# io-board-f-7.net
KiCad netlist of a schematic drawn in EAGLE
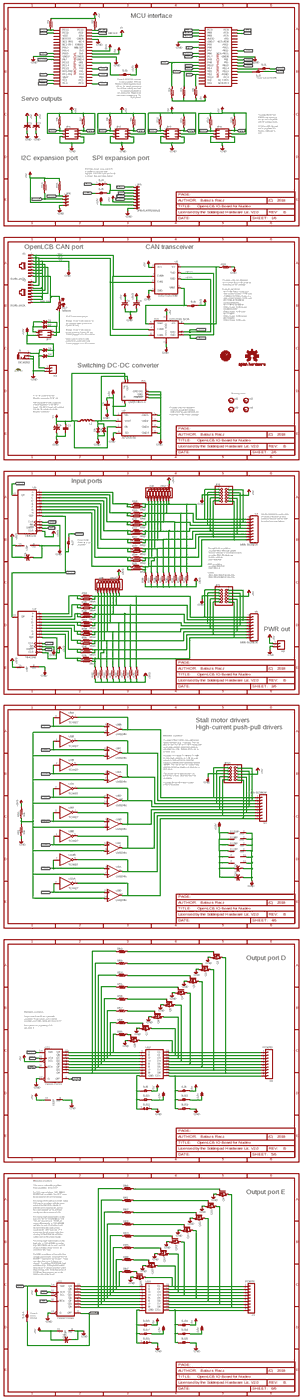
[diagram p0: schematic, sheet 1, overview]
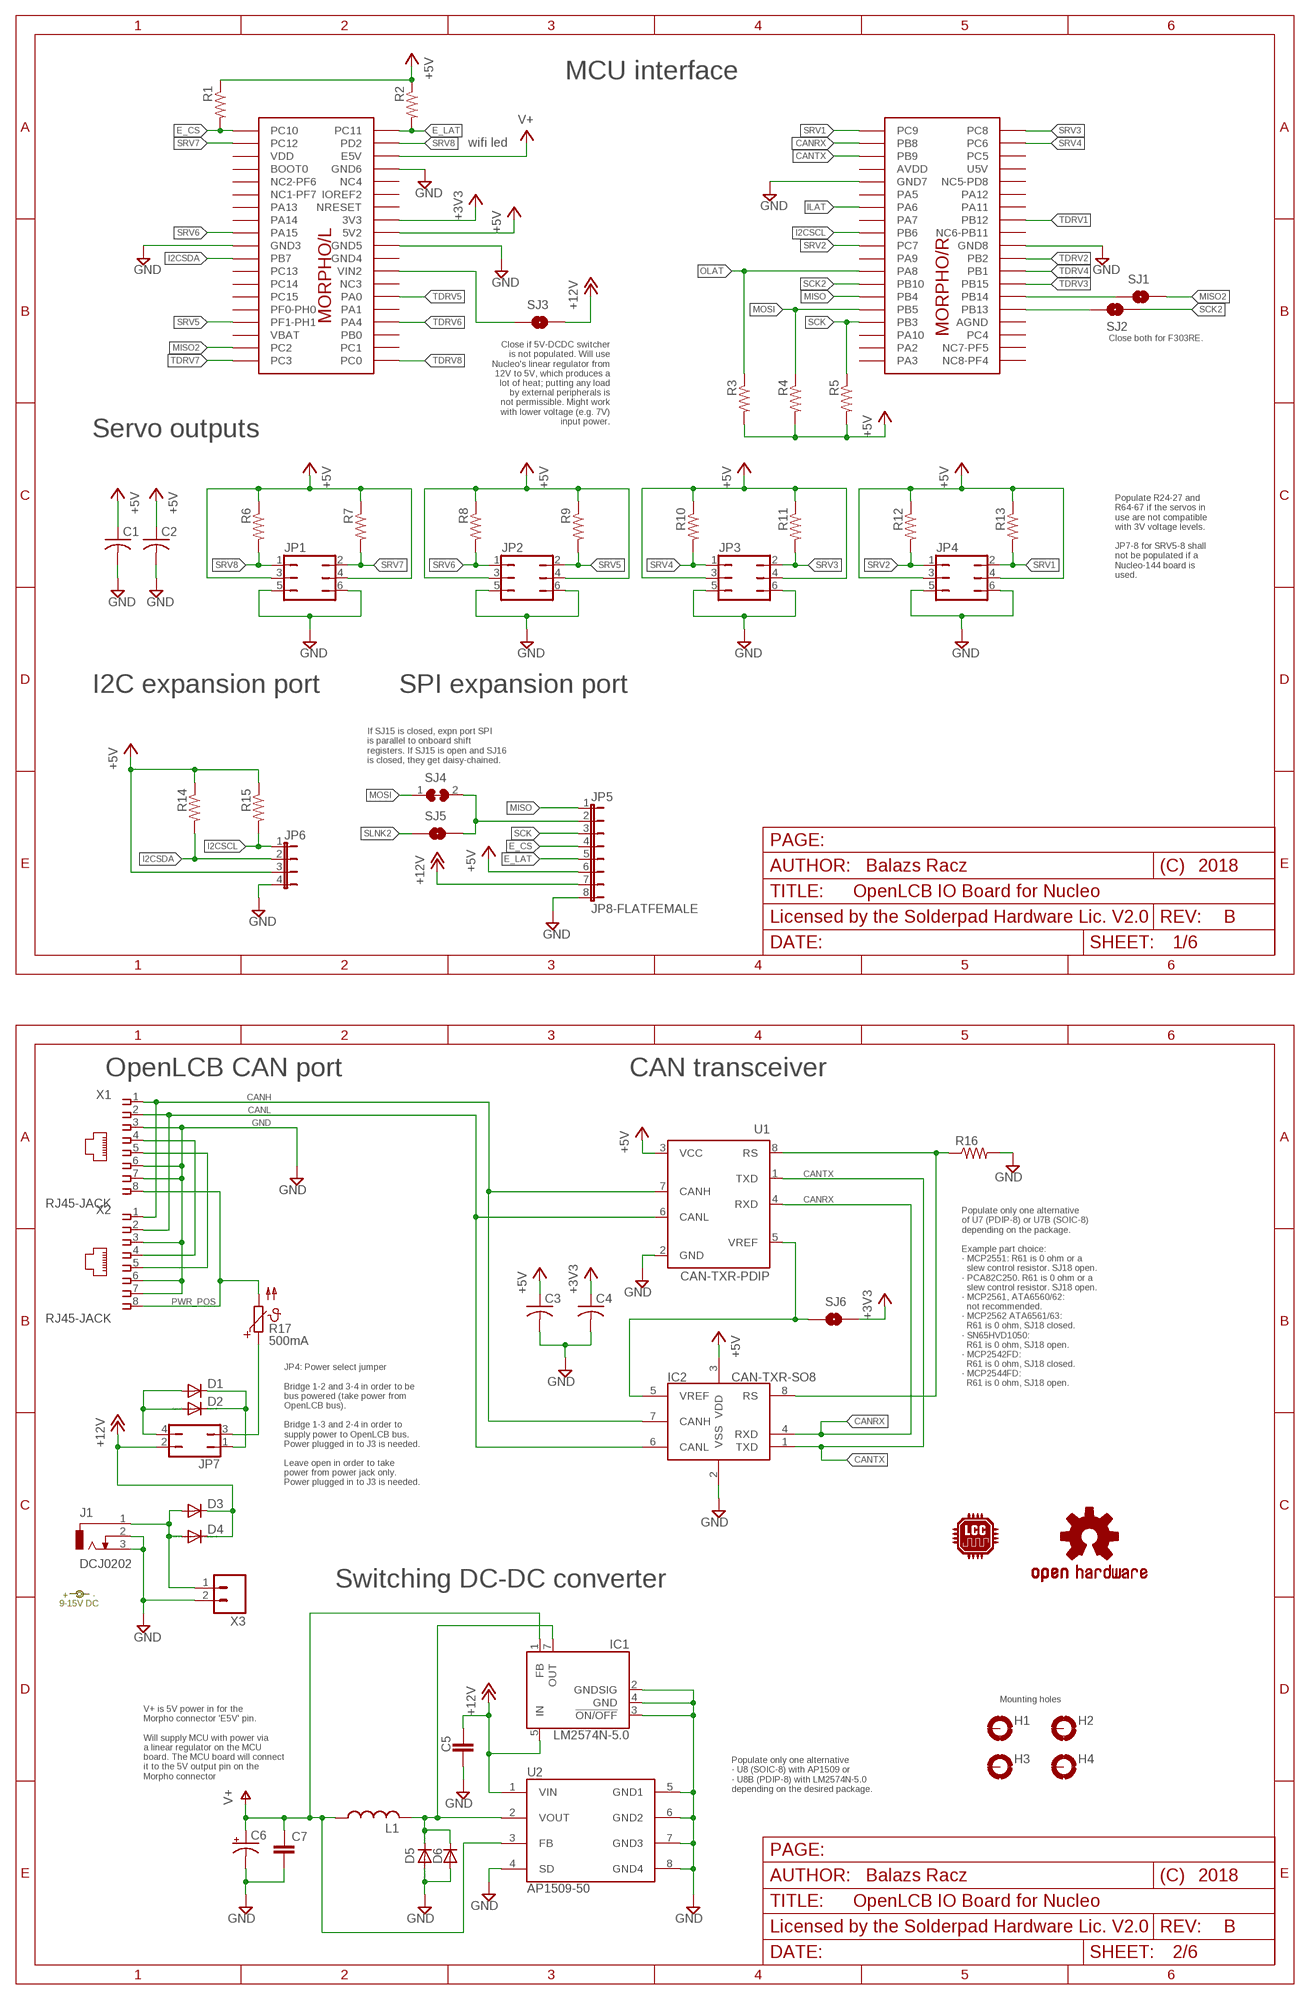
[diagram p1: schematic, sheet 1, part 1 of 4]
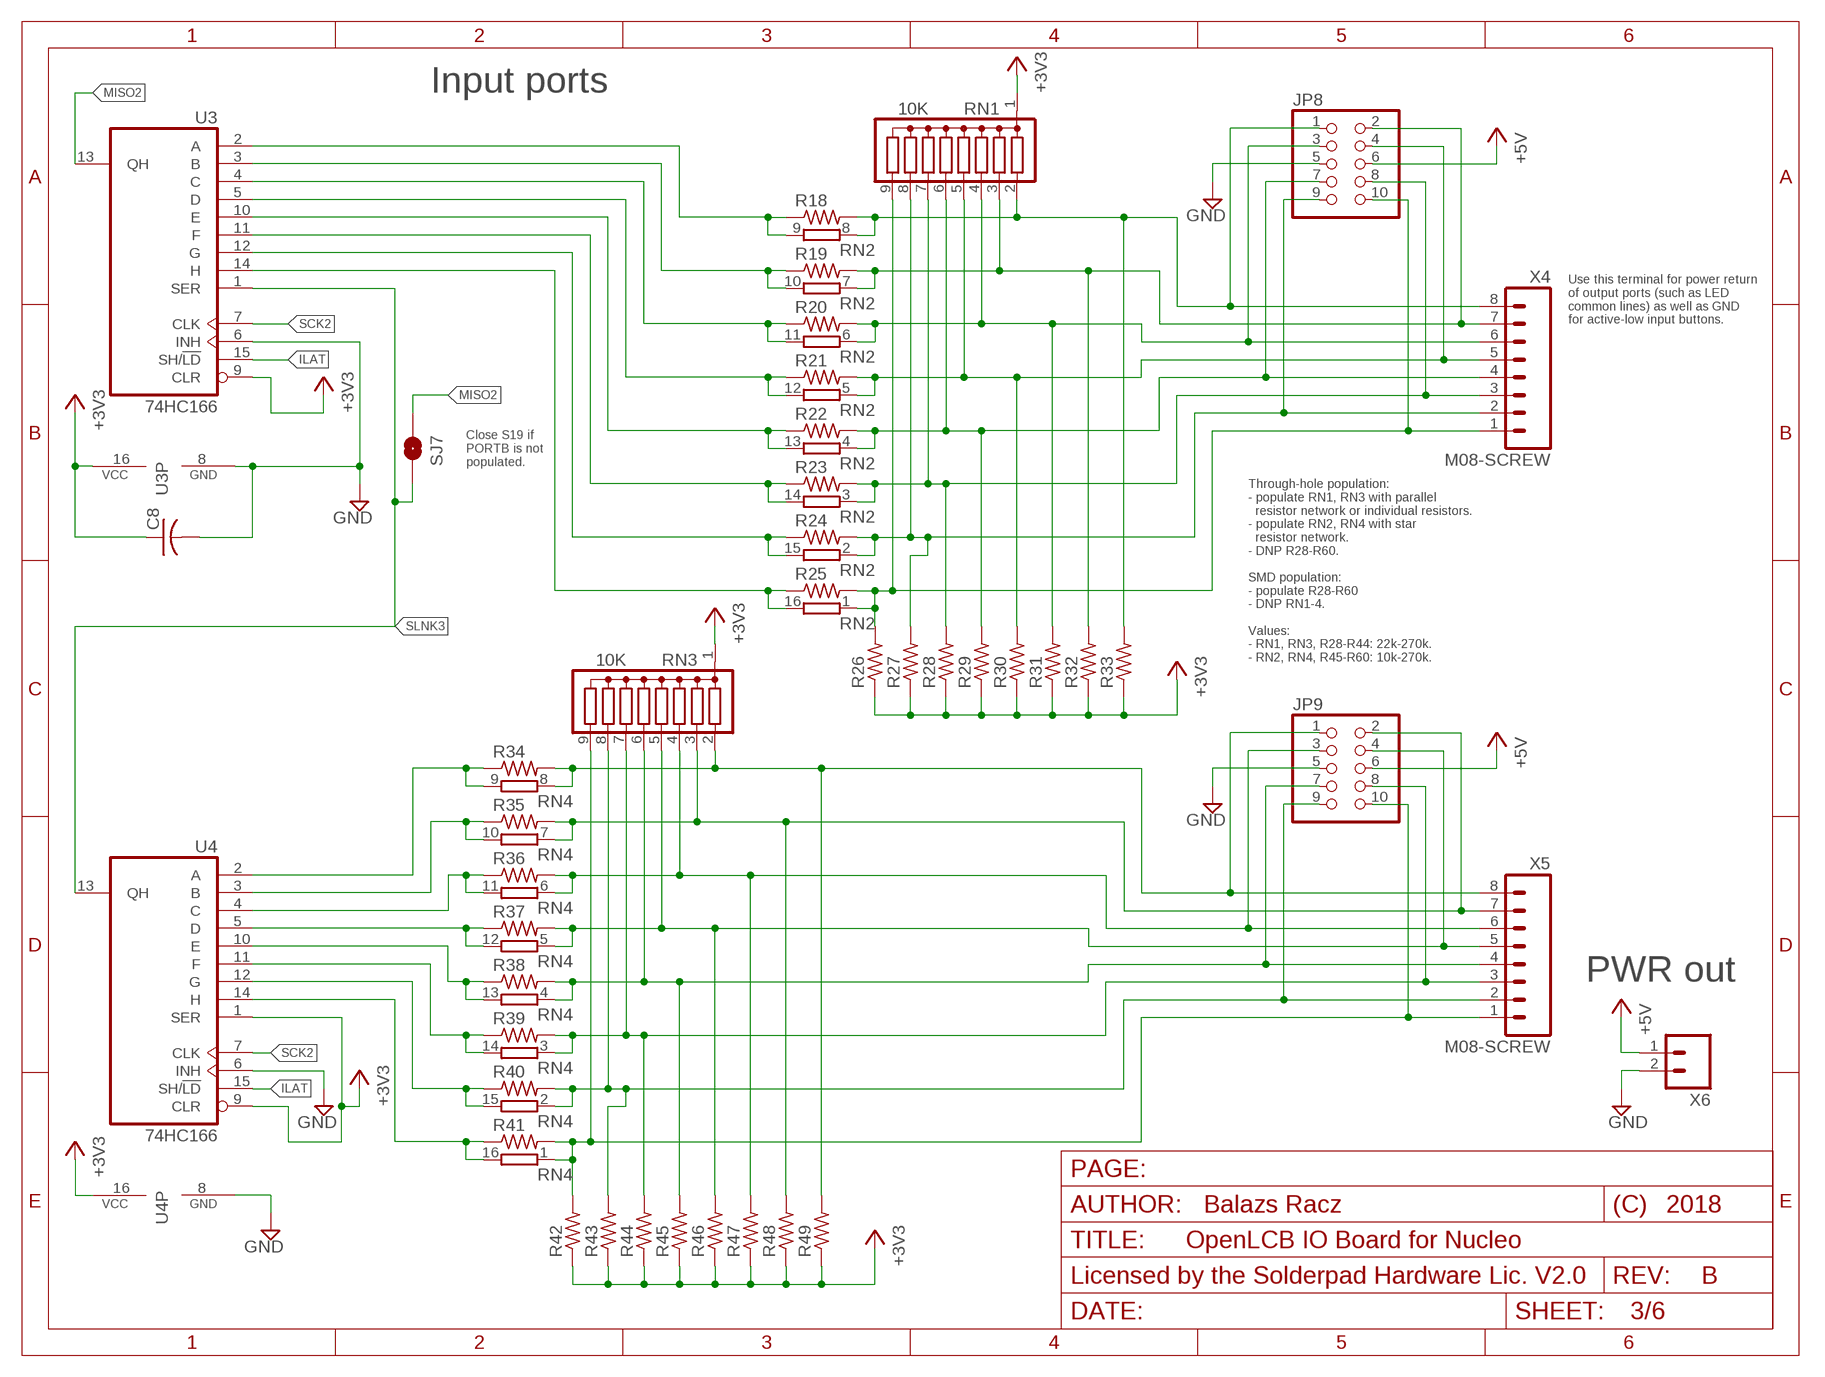
[diagram p2: schematic, sheet 1, part 2 of 4]
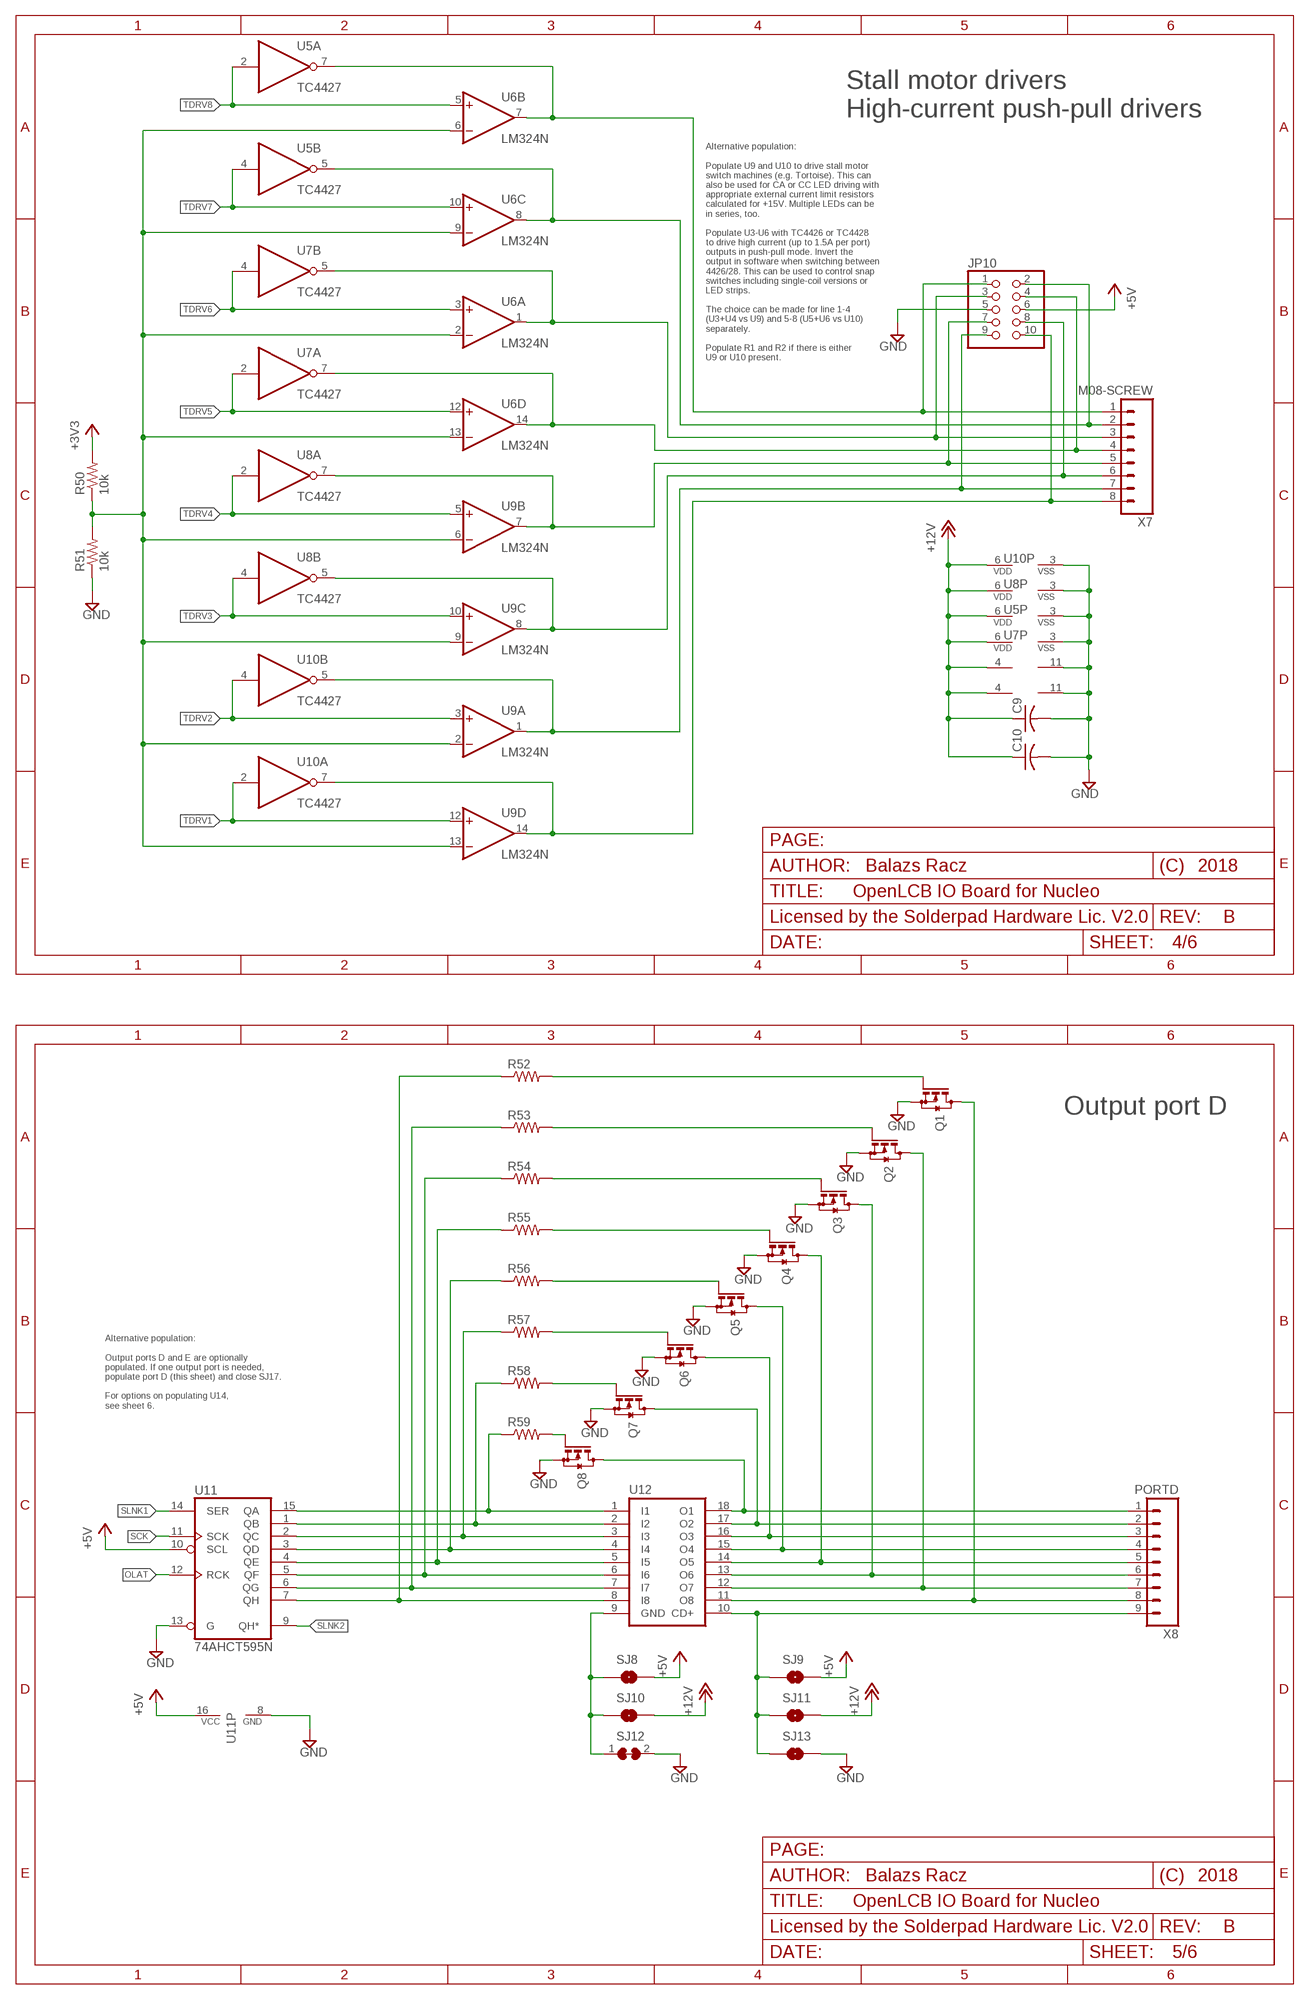
[diagram p3: schematic, sheet 1, part 3 of 4]
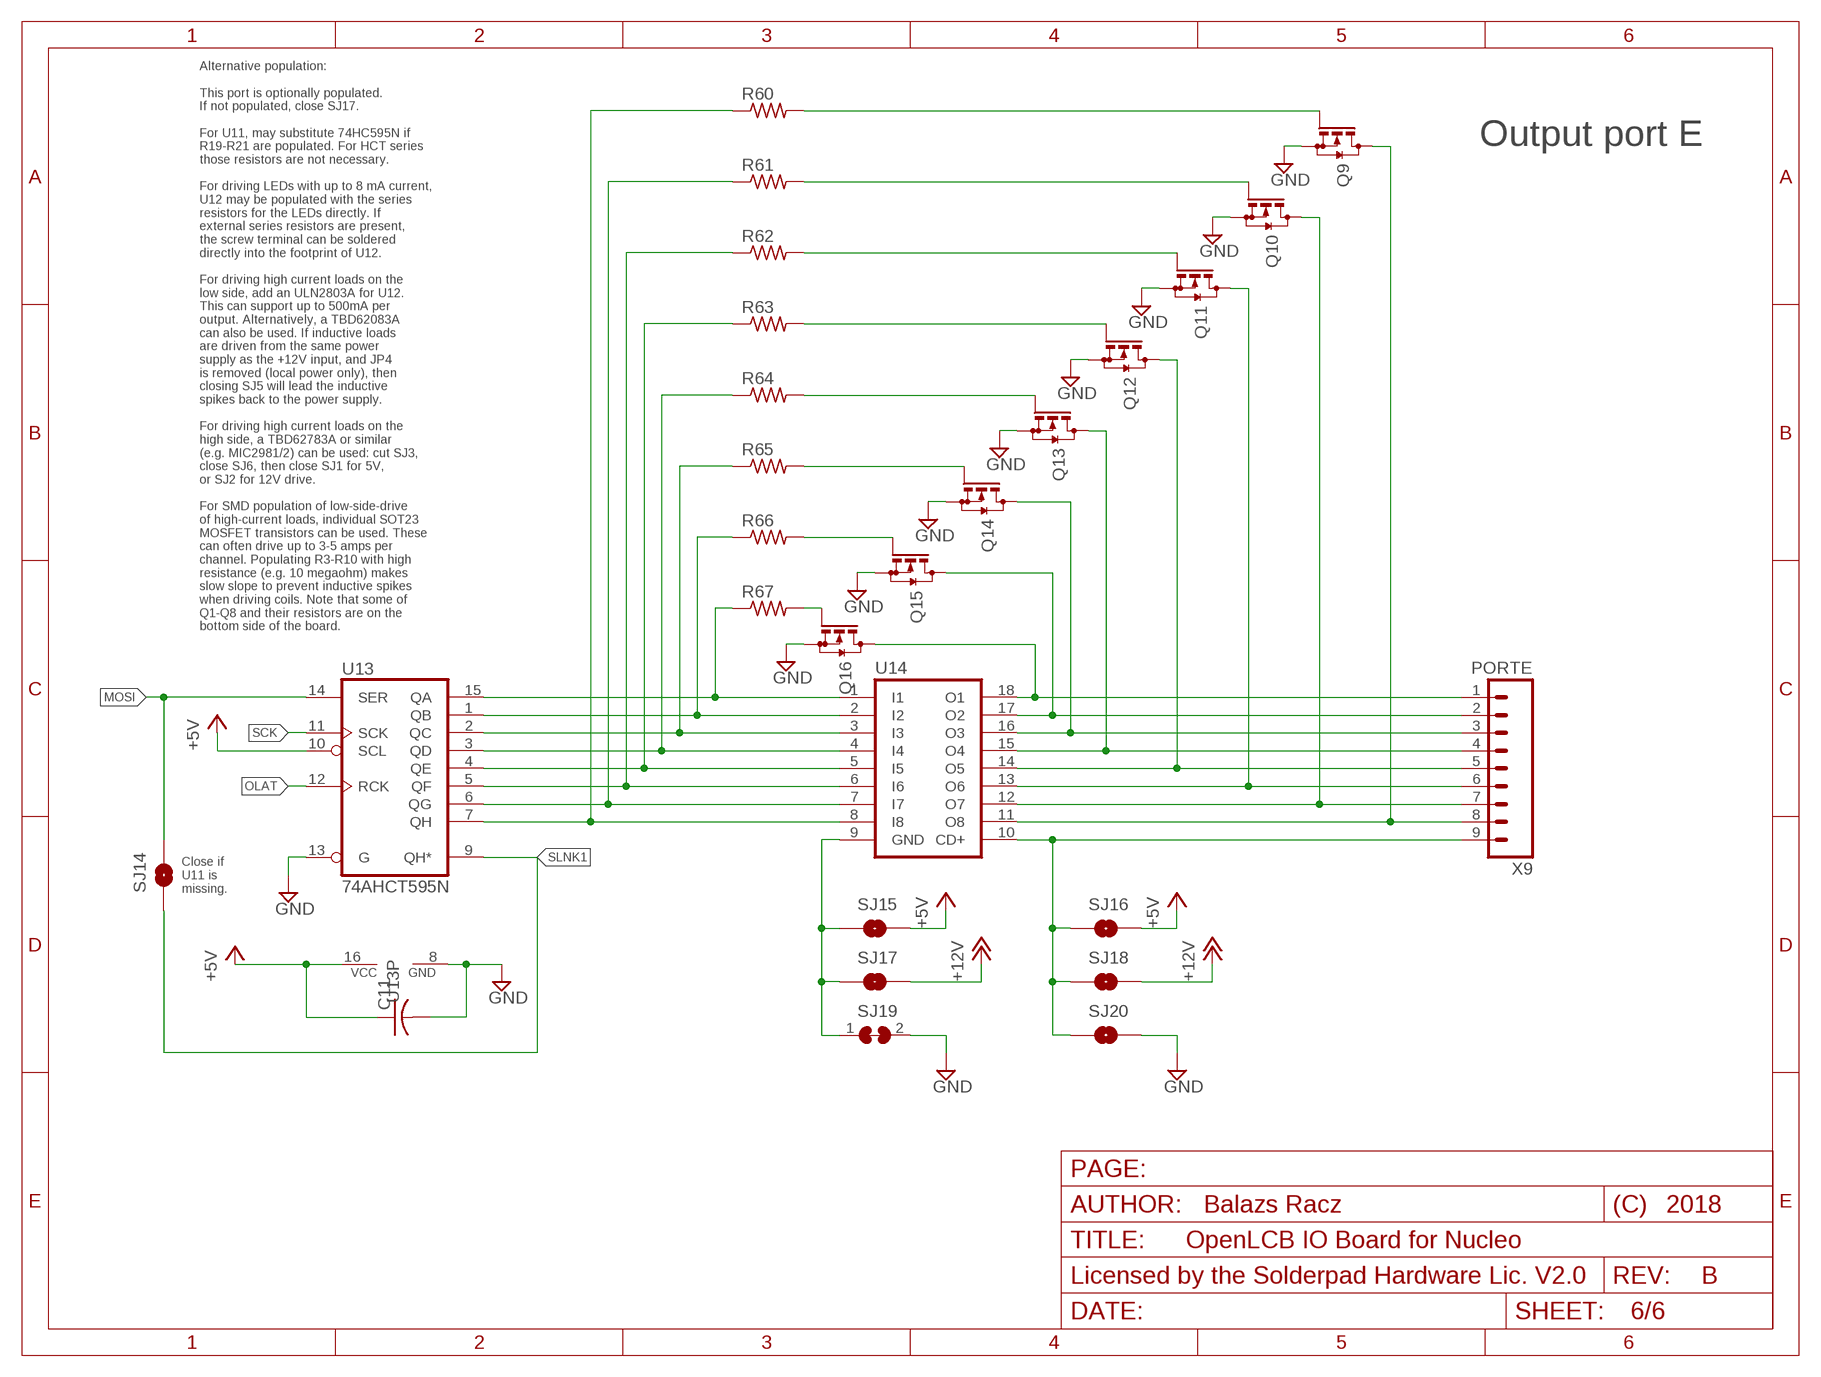
[diagram p4: schematic, sheet 1, part 4 of 4]

(export (version "E")
  (design (tool "Eeschema 10.0.6"))
  (components
    (comp (ref "C1")
      (value "C-USC1206")
      (footprint "eagle-import:C1206")
      (libsource (lib "eagle-import") (part "C-USC1206"))
    )
    (comp (ref "C2")
      (value "C-USC1206")
      (footprint "eagle-import:C1206")
      (libsource (lib "eagle-import") (part "C-USC1206"))
    )
    (comp (ref "C3")
      (value "C-USC0805")
      (footprint "eagle-import:C0805")
      (libsource (lib "eagle-import") (part "C-USC0805"))
    )
    (comp (ref "C4")
      (value "C-USC0805")
      (footprint "eagle-import:C0805")
      (libsource (lib "eagle-import") (part "C-USC0805"))
    )
    (comp (ref "C5")
      (value "C-EUC1206")
      (footprint "eagle-import:C1206")
      (libsource (lib "eagle-import") (part "C-EUC1206"))
    )
    (comp (ref "C6")
      (value "CPOL-USE2.5-5")
      (footprint "eagle-import:E2,5-5")
      (libsource (lib "eagle-import") (part "CPOL-USE2.5-5"))
    )
    (comp (ref "C7")
      (value "C-EUC1206")
      (footprint "eagle-import:C1206")
      (libsource (lib "eagle-import") (part "C-EUC1206"))
    )
    (comp (ref "C8")
      (value "C-USC0805")
      (footprint "eagle-import:C0805")
      (libsource (lib "eagle-import") (part "C-USC0805"))
    )
    (comp (ref "C9")
      (value "C-USC1206")
      (footprint "eagle-import:C1206")
      (libsource (lib "eagle-import") (part "C-USC1206"))
    )
    (comp (ref "C10")
      (value "C-USC1206")
      (footprint "eagle-import:C1206")
      (libsource (lib "eagle-import") (part "C-USC1206"))
    )
    (comp (ref "C11")
      (value "C-USC0805")
      (footprint "eagle-import:C0805")
      (libsource (lib "eagle-import") (part "C-USC0805"))
    )
    (comp (ref "D1")
      (value "DIODEDO-214AA-NODOC")
      (footprint "eagle-import:DO214AA-NODOC")
      (libsource (lib "eagle-import") (part "DIODEDO-214AA-NODOC"))
    )
    (comp (ref "D2")
      (value "DIODE-DO41-7.6")
      (footprint "eagle-import:DO41-7.6")
      (libsource (lib "eagle-import") (part "DIODE-DO41-7.6"))
    )
    (comp (ref "D3")
      (value "DIODEDO-214AA-NODOC")
      (footprint "eagle-import:DO214AA-NODOC")
      (libsource (lib "eagle-import") (part "DIODEDO-214AA-NODOC"))
    )
    (comp (ref "D4")
      (value "DIODE-DO41-7.6")
      (footprint "eagle-import:DO41-7.6")
      (libsource (lib "eagle-import") (part "DIODE-DO41-7.6"))
    )
    (comp (ref "D5")
      (value "DIODE-DO41-7.6")
      (footprint "eagle-import:DO41-7.6")
      (libsource (lib "eagle-import") (part "DIODE-DO41-7.6"))
    )
    (comp (ref "D6")
      (value "DIODEDO-214AA-NODOC")
      (footprint "eagle-import:DO214AA-NODOC")
      (libsource (lib "eagle-import") (part "DIODEDO-214AA-NODOC"))
    )
    (comp (ref "G1")
      (value "NUCLEO_64_GENERIC")
      (footprint "eagle-import:NUCLEO_BRD_BASE64")
      (libsource (lib "eagle-import") (part "NUCLEO_64_GENERIC"))
    )
    (comp (ref "H1")
      (value "MOUNT-PAD-ROUND3.3")
      (footprint "eagle-import:3,3-PAD")
      (libsource (lib "eagle-import") (part "MOUNT-PAD-ROUND3.3"))
    )
    (comp (ref "H2")
      (value "MOUNT-PAD-ROUND3.3")
      (footprint "eagle-import:3,3-PAD")
      (libsource (lib "eagle-import") (part "MOUNT-PAD-ROUND3.3"))
    )
    (comp (ref "H3")
      (value "MOUNT-PAD-ROUND3.3")
      (footprint "eagle-import:3,3-PAD")
      (libsource (lib "eagle-import") (part "MOUNT-PAD-ROUND3.3"))
    )
    (comp (ref "H4")
      (value "MOUNT-PAD-ROUND3.3")
      (footprint "eagle-import:3,3-PAD")
      (libsource (lib "eagle-import") (part "MOUNT-PAD-ROUND3.3"))
    )
    (comp (ref "IC1")
      (value "LM2574N-5.0")
      (footprint "eagle-import:DIL08")
      (libsource (lib "eagle-import") (part "LM2574?-N5.0"))
    )
    (comp (ref "IC2")
      (value "CAN-TXR-SO8")
      (footprint "eagle-import:SO-08")
      (libsource (lib "eagle-import") (part "MCP2551-SN"))
    )
    (comp (ref "J1")
      (value "DCJ0202")
      (footprint "eagle-import:DCJ0202")
      (libsource (lib "eagle-import") (part "DCJ0202"))
    )
    (comp (ref "JP1")
      (value "JP3Q")
      (footprint "eagle-import:JP3Q")
      (libsource (lib "eagle-import") (part "JP3Q"))
    )
    (comp (ref "JP2")
      (value "JP3Q")
      (footprint "eagle-import:JP3Q")
      (libsource (lib "eagle-import") (part "JP3Q"))
    )
    (comp (ref "JP3")
      (value "JP3Q")
      (footprint "eagle-import:JP3Q")
      (libsource (lib "eagle-import") (part "JP3Q"))
    )
    (comp (ref "JP4")
      (value "JP3Q")
      (footprint "eagle-import:JP3Q")
      (libsource (lib "eagle-import") (part "JP3Q"))
    )
    (comp (ref "JP5")
      (value "JP8-FLATFEMALE")
      (footprint "eagle-import:JP8F-FEM")
      (libsource (lib "eagle-import") (part "JP8-FLATFEMALE"))
    )
    (comp (ref "JP6")
      (value "JP4-FLAT")
      (footprint "eagle-import:JP4F")
      (libsource (lib "eagle-import") (part "JP4-FLAT"))
    )
    (comp (ref "JP7")
      (value "JP2Q")
      (footprint "eagle-import:JP2Q")
      (libsource (lib "eagle-import") (part "JP2Q"))
    )
    (comp (ref "JP8")
      (value "PINHD-2X5CN")
      (footprint "eagle-import:CON10M")
      (libsource (lib "eagle-import") (part "PINHD-2X5CN"))
    )
    (comp (ref "JP9")
      (value "PINHD-2X5CN")
      (footprint "eagle-import:CON10M")
      (libsource (lib "eagle-import") (part "PINHD-2X5CN"))
    )
    (comp (ref "JP10")
      (value "PINHD-2X5CN")
      (footprint "eagle-import:CON10M")
      (libsource (lib "eagle-import") (part "PINHD-2X5CN"))
    )
    (comp (ref "L1")
      (value "L-US")
      (footprint "eagle-import:L5-8,5")
      (libsource (lib "eagle-import") (part "L-US"))
    )
    (comp (ref "LG1")
      (value "LCC_LOGO")
      (footprint "eagle-import:LCC_LOGO")
      (libsource (lib "eagle-import") (part "LCC_LOGO"))
    )
    (comp (ref "LOGO1")
      (value "DOC-OSHW-LOGOM")
      (footprint "eagle-import:OSHW-LOGO-M")
      (libsource (lib "eagle-import") (part "DOC-OSHW-LOGOM"))
    )
    (comp (ref "P1")
      (value "9-15V DC")
      (footprint "eagle-import:POWER_USAGE")
      (libsource (lib "eagle-import") (part "DOC-POWER_LABEL"))
    )
    (comp (ref "Q1")
      (value "BSS123")
      (footprint "eagle-import:SOT23")
      (libsource (lib "eagle-import") (part "BSS123"))
    )
    (comp (ref "Q2")
      (value "BSS123")
      (footprint "eagle-import:SOT23")
      (libsource (lib "eagle-import") (part "BSS123"))
    )
    (comp (ref "Q3")
      (value "BSS123")
      (footprint "eagle-import:SOT23")
      (libsource (lib "eagle-import") (part "BSS123"))
    )
    (comp (ref "Q4")
      (value "BSS123")
      (footprint "eagle-import:SOT23")
      (libsource (lib "eagle-import") (part "BSS123"))
    )
    (comp (ref "Q5")
      (value "BSS123")
      (footprint "eagle-import:SOT23")
      (libsource (lib "eagle-import") (part "BSS123"))
    )
    (comp (ref "Q6")
      (value "BSS123")
      (footprint "eagle-import:SOT23")
      (libsource (lib "eagle-import") (part "BSS123"))
    )
    (comp (ref "Q7")
      (value "BSS123")
      (footprint "eagle-import:SOT23")
      (libsource (lib "eagle-import") (part "BSS123"))
    )
    (comp (ref "Q8")
      (value "BSS123")
      (footprint "eagle-import:SOT23")
      (libsource (lib "eagle-import") (part "BSS123"))
    )
    (comp (ref "Q9")
      (value "BSS123")
      (footprint "eagle-import:SOT23")
      (libsource (lib "eagle-import") (part "BSS123"))
    )
    (comp (ref "Q10")
      (value "BSS123")
      (footprint "eagle-import:SOT23")
      (libsource (lib "eagle-import") (part "BSS123"))
    )
    (comp (ref "Q11")
      (value "BSS123")
      (footprint "eagle-import:SOT23")
      (libsource (lib "eagle-import") (part "BSS123"))
    )
    (comp (ref "Q12")
      (value "BSS123")
      (footprint "eagle-import:SOT23")
      (libsource (lib "eagle-import") (part "BSS123"))
    )
    (comp (ref "Q13")
      (value "BSS123")
      (footprint "eagle-import:SOT23")
      (libsource (lib "eagle-import") (part "BSS123"))
    )
    (comp (ref "Q14")
      (value "BSS123")
      (footprint "eagle-import:SOT23")
      (libsource (lib "eagle-import") (part "BSS123"))
    )
    (comp (ref "Q15")
      (value "BSS123")
      (footprint "eagle-import:SOT23")
      (libsource (lib "eagle-import") (part "BSS123"))
    )
    (comp (ref "Q16")
      (value "BSS123")
      (footprint "eagle-import:SOT23")
      (libsource (lib "eagle-import") (part "BSS123"))
    )
    (comp (ref "R1")
      (value "R-US_R0805")
      (footprint "eagle-import:R0805")
      (libsource (lib "eagle-import") (part "rcl_334_R-US_R0805"))
    )
    (comp (ref "R2")
      (value "R-US_R0805")
      (footprint "eagle-import:R0805")
      (libsource (lib "eagle-import") (part "rcl_334_R-US_R0805"))
    )
    (comp (ref "R3")
      (value "R-US_R0805")
      (footprint "eagle-import:R0805")
      (libsource (lib "eagle-import") (part "rcl_334_R-US_R0805"))
    )
    (comp (ref "R4")
      (value "R-US_R0805")
      (footprint "eagle-import:R0805")
      (libsource (lib "eagle-import") (part "rcl_334_R-US_R0805"))
    )
    (comp (ref "R5")
      (value "R-US_R0805")
      (footprint "eagle-import:R0805")
      (libsource (lib "eagle-import") (part "rcl_334_R-US_R0805"))
    )
    (comp (ref "R6")
      (value "R-US_R0805")
      (footprint "eagle-import:R0805")
      (libsource (lib "eagle-import") (part "rcl_334_R-US_R0805"))
    )
    (comp (ref "R7")
      (value "R-US_R0805")
      (footprint "eagle-import:R0805")
      (libsource (lib "eagle-import") (part "rcl_334_R-US_R0805"))
    )
    (comp (ref "R8")
      (value "R-US_R0805")
      (footprint "eagle-import:R0805")
      (libsource (lib "eagle-import") (part "rcl_334_R-US_R0805"))
    )
    (comp (ref "R9")
      (value "R-US_R0805")
      (footprint "eagle-import:R0805")
      (libsource (lib "eagle-import") (part "rcl_334_R-US_R0805"))
    )
    (comp (ref "R10")
      (value "R-US_R0805")
      (footprint "eagle-import:R0805")
      (libsource (lib "eagle-import") (part "rcl_334_R-US_R0805"))
    )
    (comp (ref "R11")
      (value "R-US_R0805")
      (footprint "eagle-import:R0805")
      (libsource (lib "eagle-import") (part "rcl_334_R-US_R0805"))
    )
    (comp (ref "R12")
      (value "R-US_R0805")
      (footprint "eagle-import:R0805")
      (libsource (lib "eagle-import") (part "rcl_334_R-US_R0805"))
    )
    (comp (ref "R13")
      (value "R-US_R0805")
      (footprint "eagle-import:R0805")
      (libsource (lib "eagle-import") (part "rcl_334_R-US_R0805"))
    )
    (comp (ref "R14")
      (value "R-US_R0805")
      (footprint "eagle-import:R0805")
      (libsource (lib "eagle-import") (part "rcl_334_R-US_R0805"))
    )
    (comp (ref "R15")
      (value "R-US_R0805")
      (footprint "eagle-import:R0805")
      (libsource (lib "eagle-import") (part "rcl_334_R-US_R0805"))
    )
    (comp (ref "R16")
      (value "R-US_R0805")
      (footprint "eagle-import:R0805")
      (libsource (lib "eagle-import") (part "rcl_334_R-US_R0805"))
    )
    (comp (ref "R17")
      (value "500mA")
      (footprint "eagle-import:PTC1812")
      (libsource (lib "eagle-import") (part "PTC_1812"))
    )
    (comp (ref "R18")
      (value "R-US_R0603")
      (footprint "eagle-import:R0603")
      (libsource (lib "eagle-import") (part "rcl_334_R-US_R0603"))
    )
    (comp (ref "R19")
      (value "R-US_R0603")
      (footprint "eagle-import:R0603")
      (libsource (lib "eagle-import") (part "rcl_334_R-US_R0603"))
    )
    (comp (ref "R20")
      (value "R-US_R0603")
      (footprint "eagle-import:R0603")
      (libsource (lib "eagle-import") (part "rcl_334_R-US_R0603"))
    )
    (comp (ref "R21")
      (value "R-US_R0603")
      (footprint "eagle-import:R0603")
      (libsource (lib "eagle-import") (part "rcl_334_R-US_R0603"))
    )
    (comp (ref "R22")
      (value "R-US_R0603")
      (footprint "eagle-import:R0603")
      (libsource (lib "eagle-import") (part "rcl_334_R-US_R0603"))
    )
    (comp (ref "R23")
      (value "R-US_R0603")
      (footprint "eagle-import:R0603")
      (libsource (lib "eagle-import") (part "rcl_334_R-US_R0603"))
    )
    (comp (ref "R24")
      (value "R-US_R0603")
      (footprint "eagle-import:R0603")
      (libsource (lib "eagle-import") (part "rcl_334_R-US_R0603"))
    )
    (comp (ref "R25")
      (value "R-US_R0603")
      (footprint "eagle-import:R0603")
      (libsource (lib "eagle-import") (part "rcl_334_R-US_R0603"))
    )
    (comp (ref "R26")
      (value "R-US")
      (footprint "eagle-import:R0603")
      (libsource (lib "eagle-import") (part "R-US"))
    )
    (comp (ref "R27")
      (value "R-US")
      (footprint "eagle-import:R0603")
      (libsource (lib "eagle-import") (part "R-US"))
    )
    (comp (ref "R28")
      (value "R-US")
      (footprint "eagle-import:R0603")
      (libsource (lib "eagle-import") (part "R-US"))
    )
    (comp (ref "R29")
      (value "R-US")
      (footprint "eagle-import:R0603")
      (libsource (lib "eagle-import") (part "R-US"))
    )
    (comp (ref "R30")
      (value "R-US")
      (footprint "eagle-import:R0603")
      (libsource (lib "eagle-import") (part "R-US"))
    )
    (comp (ref "R31")
      (value "R-US")
      (footprint "eagle-import:R0603")
      (libsource (lib "eagle-import") (part "R-US"))
    )
    (comp (ref "R32")
      (value "R-US")
      (footprint "eagle-import:R0603")
      (libsource (lib "eagle-import") (part "R-US"))
    )
    (comp (ref "R33")
      (value "R-US")
      (footprint "eagle-import:R0603")
      (libsource (lib "eagle-import") (part "R-US"))
    )
    (comp (ref "R34")
      (value "R-US_R0603")
      (footprint "eagle-import:R0603")
      (libsource (lib "eagle-import") (part "rcl_334_R-US_R0603"))
    )
    (comp (ref "R35")
      (value "R-US_R0603")
      (footprint "eagle-import:R0603")
      (libsource (lib "eagle-import") (part "rcl_334_R-US_R0603"))
    )
    (comp (ref "R36")
      (value "R-US_R0603")
      (footprint "eagle-import:R0603")
      (libsource (lib "eagle-import") (part "rcl_334_R-US_R0603"))
    )
    (comp (ref "R37")
      (value "R-US_R0603")
      (footprint "eagle-import:R0603")
      (libsource (lib "eagle-import") (part "rcl_334_R-US_R0603"))
    )
    (comp (ref "R38")
      (value "R-US_R0603")
      (footprint "eagle-import:R0603")
      (libsource (lib "eagle-import") (part "rcl_334_R-US_R0603"))
    )
    (comp (ref "R39")
      (value "R-US_R0603")
      (footprint "eagle-import:R0603")
      (libsource (lib "eagle-import") (part "rcl_334_R-US_R0603"))
    )
    (comp (ref "R40")
      (value "R-US_R0603")
      (footprint "eagle-import:R0603")
      (libsource (lib "eagle-import") (part "rcl_334_R-US_R0603"))
    )
    (comp (ref "R41")
      (value "R-US_R0603")
      (footprint "eagle-import:R0603")
      (libsource (lib "eagle-import") (part "rcl_334_R-US_R0603"))
    )
    (comp (ref "R42")
      (value "R-US")
      (footprint "eagle-import:R0603")
      (libsource (lib "eagle-import") (part "R-US"))
    )
    (comp (ref "R43")
      (value "R-US")
      (footprint "eagle-import:R0603")
      (libsource (lib "eagle-import") (part "R-US"))
    )
    (comp (ref "R44")
      (value "R-US")
      (footprint "eagle-import:R0603")
      (libsource (lib "eagle-import") (part "R-US"))
    )
    (comp (ref "R45")
      (value "R-US")
      (footprint "eagle-import:R0603")
      (libsource (lib "eagle-import") (part "R-US"))
    )
    (comp (ref "R46")
      (value "R-US")
      (footprint "eagle-import:R0603")
      (libsource (lib "eagle-import") (part "R-US"))
    )
    (comp (ref "R47")
      (value "R-US")
      (footprint "eagle-import:R0603")
      (libsource (lib "eagle-import") (part "R-US"))
    )
    (comp (ref "R48")
      (value "R-US")
      (footprint "eagle-import:R0603")
      (libsource (lib "eagle-import") (part "R-US"))
    )
    (comp (ref "R49")
      (value "R-US")
      (footprint "eagle-import:R0603")
      (libsource (lib "eagle-import") (part "R-US"))
    )
    (comp (ref "R50")
      (value "10k")
      (footprint "eagle-import:R0805")
      (libsource (lib "eagle-import") (part "R-US_R0805"))
    )
    (comp (ref "R51")
      (value "10k")
      (footprint "eagle-import:R0805")
      (libsource (lib "eagle-import") (part "R-US_R0805"))
    )
    (comp (ref "R52")
      (value "R-US_R0603")
      (footprint "eagle-import:R0603")
      (libsource (lib "eagle-import") (part "R-US_R0603"))
    )
    (comp (ref "R53")
      (value "R-US_R0603")
      (footprint "eagle-import:R0603")
      (libsource (lib "eagle-import") (part "R-US_R0603"))
    )
    (comp (ref "R54")
      (value "R-US_R0603")
      (footprint "eagle-import:R0603")
      (libsource (lib "eagle-import") (part "R-US_R0603"))
    )
    (comp (ref "R55")
      (value "R-US_R0603")
      (footprint "eagle-import:R0603")
      (libsource (lib "eagle-import") (part "R-US_R0603"))
    )
    (comp (ref "R56")
      (value "R-US_R0603")
      (footprint "eagle-import:R0603")
      (libsource (lib "eagle-import") (part "R-US_R0603"))
    )
    (comp (ref "R57")
      (value "R-US_R0603")
      (footprint "eagle-import:R0603")
      (libsource (lib "eagle-import") (part "R-US_R0603"))
    )
    (comp (ref "R58")
      (value "R-US_R0603")
      (footprint "eagle-import:R0603")
      (libsource (lib "eagle-import") (part "R-US_R0603"))
    )
    (comp (ref "R59")
      (value "R-US_R0603")
      (footprint "eagle-import:R0603")
      (libsource (lib "eagle-import") (part "R-US_R0603"))
    )
    (comp (ref "R60")
      (value "R-US_R0603")
      (footprint "eagle-import:R0603")
      (libsource (lib "eagle-import") (part "R-US_R0603"))
    )
    (comp (ref "R61")
      (value "R-US_R0603")
      (footprint "eagle-import:R0603")
      (libsource (lib "eagle-import") (part "R-US_R0603"))
    )
    (comp (ref "R62")
      (value "R-US_R0603")
      (footprint "eagle-import:R0603")
      (libsource (lib "eagle-import") (part "R-US_R0603"))
    )
    (comp (ref "R63")
      (value "R-US_R0603")
      (footprint "eagle-import:R0603")
      (libsource (lib "eagle-import") (part "R-US_R0603"))
    )
    (comp (ref "R64")
      (value "R-US_R0603")
      (footprint "eagle-import:R0603")
      (libsource (lib "eagle-import") (part "R-US_R0603"))
    )
    (comp (ref "R65")
      (value "R-US_R0603")
      (footprint "eagle-import:R0603")
      (libsource (lib "eagle-import") (part "R-US_R0603"))
    )
    (comp (ref "R66")
      (value "R-US_R0603")
      (footprint "eagle-import:R0603")
      (libsource (lib "eagle-import") (part "R-US_R0603"))
    )
    (comp (ref "R67")
      (value "R-US_R0603")
      (footprint "eagle-import:R0603")
      (libsource (lib "eagle-import") (part "R-US_R0603"))
    )
    (comp (ref "RN1")
      (value "10K")
      (footprint "eagle-import:SIL9")
      (libsource (lib "eagle-import") (part "G08R"))
    )
    (comp (ref "RN2")
      (value "8R-P")
      (footprint "eagle-import:DIL16")
      (libsource (lib "eagle-import") (part "8R-P"))
    )
    (comp (ref "RN3")
      (value "10K")
      (footprint "eagle-import:SIL9")
      (libsource (lib "eagle-import") (part "G08R"))
    )
    (comp (ref "RN4")
      (value "8R-P")
      (footprint "eagle-import:DIL16")
      (libsource (lib "eagle-import") (part "8R-P"))
    )
    (comp (ref "SJ1")
      (value "SJRND2")
      (footprint "eagle-import:SJ_RND2")
      (libsource (lib "eagle-import") (part "SJRND2"))
    )
    (comp (ref "SJ2")
      (value "SJRND2")
      (footprint "eagle-import:SJ_RND2")
      (libsource (lib "eagle-import") (part "SJRND2"))
    )
    (comp (ref "SJ3")
      (value "SJRND2")
      (footprint "eagle-import:SJ_RND2")
      (libsource (lib "eagle-import") (part "SJRND2"))
    )
    (comp (ref "SJ4")
      (value "SJ-C")
      (footprint "eagle-import:SJW-C")
      (libsource (lib "eagle-import") (part "SJ-C"))
    )
    (comp (ref "SJ5")
      (value "SJRND2")
      (footprint "eagle-import:SJ_RND2")
      (libsource (lib "eagle-import") (part "SJRND2"))
    )
    (comp (ref "SJ6")
      (value "SJRND2")
      (footprint "eagle-import:SJ_RND2")
      (libsource (lib "eagle-import") (part "SJRND2"))
    )
    (comp (ref "SJ7")
      (value "SJRND2")
      (footprint "eagle-import:SJ_RND2")
      (libsource (lib "eagle-import") (part "SJRND2"))
    )
    (comp (ref "SJ8")
      (value "SJRND2")
      (footprint "eagle-import:SJ_RND2")
      (libsource (lib "eagle-import") (part "SJRND2"))
    )
    (comp (ref "SJ9")
      (value "SJRND2")
      (footprint "eagle-import:SJ_RND2")
      (libsource (lib "eagle-import") (part "SJRND2"))
    )
    (comp (ref "SJ10")
      (value "SJRND2")
      (footprint "eagle-import:SJ_RND2")
      (libsource (lib "eagle-import") (part "SJRND2"))
    )
    (comp (ref "SJ11")
      (value "SJRND2")
      (footprint "eagle-import:SJ_RND2")
      (libsource (lib "eagle-import") (part "SJRND2"))
    )
    (comp (ref "SJ12")
      (value "SJ-C")
      (footprint "eagle-import:SJW-C")
      (libsource (lib "eagle-import") (part "SJ-C"))
    )
    (comp (ref "SJ13")
      (value "SJRND2")
      (footprint "eagle-import:SJ_RND2")
      (libsource (lib "eagle-import") (part "SJRND2"))
    )
    (comp (ref "SJ14")
      (value "SJRND2")
      (footprint "eagle-import:SJ_RND2")
      (libsource (lib "eagle-import") (part "SJRND2"))
    )
    (comp (ref "SJ15")
      (value "SJRND2")
      (footprint "eagle-import:SJ_RND2")
      (libsource (lib "eagle-import") (part "SJRND2"))
    )
    (comp (ref "SJ16")
      (value "SJRND2")
      (footprint "eagle-import:SJ_RND2")
      (libsource (lib "eagle-import") (part "SJRND2"))
    )
    (comp (ref "SJ17")
      (value "SJRND2")
      (footprint "eagle-import:SJ_RND2")
      (libsource (lib "eagle-import") (part "SJRND2"))
    )
    (comp (ref "SJ18")
      (value "SJRND2")
      (footprint "eagle-import:SJ_RND2")
      (libsource (lib "eagle-import") (part "SJRND2"))
    )
    (comp (ref "SJ19")
      (value "SJ-C")
      (footprint "eagle-import:SJW-C")
      (libsource (lib "eagle-import") (part "SJ-C"))
    )
    (comp (ref "SJ20")
      (value "SJRND2")
      (footprint "eagle-import:SJ_RND2")
      (libsource (lib "eagle-import") (part "SJRND2"))
    )
    (comp (ref "U1")
      (value "CAN-TXR-PDIP")
      (footprint "eagle-import:DIL08")
      (libsource (lib "eagle-import") (part "PCA82C250"))
    )
    (comp (ref "U2")
      (value "AP1509-50")
      (footprint "eagle-import:SO-08")
      (libsource (lib "eagle-import") (part "AP1509"))
    )
    (comp (ref "U3")
      (value "74HC166")
      (footprint "eagle-import:DIL16")
      (libsource (lib "eagle-import") (part "74166N"))
    )
    (comp (ref "U4")
      (value "74HC166")
      (footprint "eagle-import:DIL16")
      (libsource (lib "eagle-import") (part "74166N"))
    )
    (comp (ref "U5")
      (value "TC4427")
      (footprint "eagle-import:DIL08-LONG")
      (libsource (lib "eagle-import") (part "TC4426APDIP"))
    )
    (comp (ref "U6")
      (value "LM324N")
      (footprint "eagle-import:DIL14")
      (libsource (lib "eagle-import") (part "LM324N"))
    )
    (comp (ref "U7")
      (value "TC4427")
      (footprint "eagle-import:DIL08-LONG")
      (libsource (lib "eagle-import") (part "TC4426APDIP"))
    )
    (comp (ref "U8")
      (value "TC4427")
      (footprint "eagle-import:DIL08-LONG")
      (libsource (lib "eagle-import") (part "TC4426APDIP"))
    )
    (comp (ref "U9")
      (value "LM324N")
      (footprint "eagle-import:DIL14")
      (libsource (lib "eagle-import") (part "LM324N"))
    )
    (comp (ref "U10")
      (value "TC4427")
      (footprint "eagle-import:DIL08-LONG")
      (libsource (lib "eagle-import") (part "TC4426APDIP"))
    )
    (comp (ref "U11")
      (value "74AHCT595N")
      (footprint "eagle-import:DIL16")
      (libsource (lib "eagle-import") (part "74595NHCT"))
    )
    (comp (ref "U12")
      (value "ULN2803A")
      (footprint "eagle-import:DIL18-THIN")
      (libsource (lib "eagle-import") (part "ULN2803A"))
    )
    (comp (ref "U13")
      (value "74AHCT595N")
      (footprint "eagle-import:DIL16")
      (libsource (lib "eagle-import") (part "74595NHCT"))
    )
    (comp (ref "U14")
      (value "ULN2803A")
      (footprint "eagle-import:DIL18-THIN")
      (libsource (lib "eagle-import") (part "ULN2803A"))
    )
    (comp (ref "X1")
      (value "RJ45-JACK")
      (footprint "eagle-import:RJ45-PULSE-E5J88")
      (libsource (lib "eagle-import") (part "RJ45-JACKRJ45-PULSE-E5J00"))
    )
    (comp (ref "X2")
      (value "RJ45-JACK")
      (footprint "eagle-import:RJ45-PULSE-E5J88")
      (libsource (lib "eagle-import") (part "RJ45-JACKRJ45-PULSE-E5J00"))
    )
    (comp (ref "X3")
      (value "CONNECTOR-M023.5MM-LOCK")
      (footprint "eagle-import:SCREWTERMINAL-3.5MM-2_LOCK")
      (libsource (lib "eagle-import") (part "CONNECTOR-M023.5MM-LOCK"))
    )
    (comp (ref "X4")
      (value "M08-SCREW")
      (footprint "eagle-import:1X08_TERMINAL")
      (libsource (lib "eagle-import") (part "M08-SCREW"))
    )
    (comp (ref "X5")
      (value "M08-SCREW")
      (footprint "eagle-import:1X08_TERMINAL")
      (libsource (lib "eagle-import") (part "M08-SCREW"))
    )
    (comp (ref "X6")
      (value "CONNECTOR-M023.5MM-LOCK")
      (footprint "eagle-import:SCREWTERMINAL-3.5MM-2_LOCK")
      (libsource (lib "eagle-import") (part "CONNECTOR-M023.5MM-LOCK"))
    )
    (comp (ref "X7")
      (value "M08-SCREW")
      (footprint "eagle-import:1X08_TERMINAL")
      (libsource (lib "eagle-import") (part "M08-SCREW"))
    )
    (comp (ref "X8")
      (value "PORTD")
      (footprint "eagle-import:1X09_TERMINAL")
      (libsource (lib "eagle-import") (part "M09-SCREW"))
    )
    (comp (ref "X9")
      (value "PORTE")
      (footprint "eagle-import:1X09_TERMINAL")
      (libsource (lib "eagle-import") (part "M09-SCREW"))
    )
  )
  (nets
    (net (code "1") (name "+3V3") (class "Default")
      (node (ref "C4") (pin "1") (pinfunction "1_1") (pintype "passive"))
      (node (ref "C8") (pin "1") (pinfunction "1_1") (pintype "passive"))
      (node (ref "G1") (pin "3V3") (pinfunction "3V3_3V3") (pintype "power_in"))
      (node (ref "R26") (pin "1") (pinfunction "1_1") (pintype "passive"))
      (node (ref "R27") (pin "1") (pinfunction "1_1") (pintype "passive"))
      (node (ref "R28") (pin "1") (pinfunction "1_1") (pintype "passive"))
      (node (ref "R29") (pin "1") (pinfunction "1_1") (pintype "passive"))
      (node (ref "R30") (pin "1") (pinfunction "1_1") (pintype "passive"))
      (node (ref "R31") (pin "1") (pinfunction "1_1") (pintype "passive"))
      (node (ref "R32") (pin "1") (pinfunction "1_1") (pintype "passive"))
      (node (ref "R33") (pin "1") (pinfunction "1_1") (pintype "passive"))
      (node (ref "R42") (pin "1") (pinfunction "1_1") (pintype "passive"))
      (node (ref "R43") (pin "1") (pinfunction "1_1") (pintype "passive"))
      (node (ref "R44") (pin "1") (pinfunction "1_1") (pintype "passive"))
      (node (ref "R45") (pin "1") (pinfunction "1_1") (pintype "passive"))
      (node (ref "R46") (pin "1") (pinfunction "1_1") (pintype "passive"))
      (node (ref "R47") (pin "1") (pinfunction "1_1") (pintype "passive"))
      (node (ref "R48") (pin "1") (pinfunction "1_1") (pintype "passive"))
      (node (ref "R49") (pin "1") (pinfunction "1_1") (pintype "passive"))
      (node (ref "R50") (pin "2") (pinfunction "2_2") (pintype "passive"))
      (node (ref "RN1") (pin "1") (pinfunction "1_1") (pintype "passive"))
      (node (ref "RN3") (pin "1") (pinfunction "1_1") (pintype "passive"))
      (node (ref "SJ6") (pin "P$1") (pinfunction "1_P$1") (pintype "passive"))
      (node (ref "U3") (pin "16") (pinfunction "VCC_16") (pintype "power_in"))
      (node (ref "U3") (pin "9") (pinfunction "CLR_9") (pintype "input"))
      (node (ref "U4") (pin "1") (pinfunction "SER_1") (pintype "input"))
      (node (ref "U4") (pin "16") (pinfunction "VCC_16") (pintype "power_in"))
      (node (ref "U4") (pin "9") (pinfunction "CLR_9") (pintype "input"))
    )
    (net (code "2") (name "+5V") (class "Default")
      (node (ref "C1") (pin "1") (pinfunction "1_1") (pintype "passive"))
      (node (ref "C11") (pin "1") (pinfunction "1_1") (pintype "passive"))
      (node (ref "C2") (pin "1") (pinfunction "1_1") (pintype "passive"))
      (node (ref "C3") (pin "1") (pinfunction "1_1") (pintype "passive"))
      (node (ref "G1") (pin "5V2") (pinfunction "5V2_5V2") (pintype "power_in"))
      (node (ref "IC2") (pin "3") (pinfunction "VDD_3") (pintype "power_in"))
      (node (ref "JP1") (pin "3") (pinfunction "3_3") (pintype "passive"))
      (node (ref "JP1") (pin "4") (pinfunction "4_4") (pintype "passive"))
      (node (ref "JP10") (pin "6") (pinfunction "6_6") (pintype "passive"))
      (node (ref "JP2") (pin "3") (pinfunction "3_3") (pintype "passive"))
      (node (ref "JP2") (pin "4") (pinfunction "4_4") (pintype "passive"))
      (node (ref "JP3") (pin "3") (pinfunction "3_3") (pintype "passive"))
      (node (ref "JP3") (pin "4") (pinfunction "4_4") (pintype "passive"))
      (node (ref "JP4") (pin "3") (pinfunction "3_3") (pintype "passive"))
      (node (ref "JP4") (pin "4") (pinfunction "4_4") (pintype "passive"))
      (node (ref "JP5") (pin "6") (pinfunction "6_6") (pintype "passive"))
      (node (ref "JP6") (pin "3") (pinfunction "3_3") (pintype "passive"))
      (node (ref "JP8") (pin "6") (pinfunction "6_6") (pintype "passive"))
      (node (ref "JP9") (pin "6") (pinfunction "6_6") (pintype "passive"))
      (node (ref "R1") (pin "1") (pinfunction "1_1") (pintype "passive"))
      (node (ref "R10") (pin "1") (pinfunction "1_1") (pintype "passive"))
      (node (ref "R11") (pin "1") (pinfunction "1_1") (pintype "passive"))
      (node (ref "R12") (pin "1") (pinfunction "1_1") (pintype "passive"))
      (node (ref "R13") (pin "1") (pinfunction "1_1") (pintype "passive"))
      (node (ref "R14") (pin "1") (pinfunction "1_1") (pintype "passive"))
      (node (ref "R15") (pin "1") (pinfunction "1_1") (pintype "passive"))
      (node (ref "R2") (pin "1") (pinfunction "1_1") (pintype "passive"))
      (node (ref "R3") (pin "2") (pinfunction "2_2") (pintype "passive"))
      (node (ref "R4") (pin "2") (pinfunction "2_2") (pintype "passive"))
      (node (ref "R5") (pin "2") (pinfunction "2_2") (pintype "passive"))
      (node (ref "R6") (pin "1") (pinfunction "1_1") (pintype "passive"))
      (node (ref "R7") (pin "1") (pinfunction "1_1") (pintype "passive"))
      (node (ref "R8") (pin "1") (pinfunction "1_1") (pintype "passive"))
      (node (ref "R9") (pin "1") (pinfunction "1_1") (pintype "passive"))
      (node (ref "SJ15") (pin "P$2") (pinfunction "2_P$2") (pintype "passive"))
      (node (ref "SJ16") (pin "P$2") (pinfunction "2_P$2") (pintype "passive"))
      (node (ref "SJ8") (pin "P$2") (pinfunction "2_P$2") (pintype "passive"))
      (node (ref "SJ9") (pin "P$2") (pinfunction "2_P$2") (pintype "passive"))
      (node (ref "U1") (pin "3") (pinfunction "VCC_3") (pintype "power_in"))
      (node (ref "U11") (pin "10") (pinfunction "SCL_10") (pintype "input"))
      (node (ref "U11") (pin "16") (pinfunction "VCC_16") (pintype "power_in"))
      (node (ref "U13") (pin "10") (pinfunction "SCL_10") (pintype "input"))
      (node (ref "U13") (pin "16") (pinfunction "VCC_16") (pintype "power_in"))
      (node (ref "X6") (pin "1") (pinfunction "1_1") (pintype "passive"))
    )
    (net (code "3") (name "+12V") (class "Default")
      (node (ref "C10") (pin "1") (pinfunction "1_1") (pintype "passive"))
      (node (ref "C5") (pin "1") (pinfunction "1_1") (pintype "passive"))
      (node (ref "C9") (pin "1") (pinfunction "1_1") (pintype "passive"))
      (node (ref "D3") (pin "C") (pinfunction "C_C") (pintype "passive"))
      (node (ref "D4") (pin "C") (pinfunction "C_C") (pintype "passive"))
      (node (ref "IC1") (pin "5") (pinfunction "IN_5") (pintype "input"))
      (node (ref "JP5") (pin "7") (pinfunction "7_7") (pintype "passive"))
      (node (ref "JP7") (pin "2") (pinfunction "2_2") (pintype "passive"))
      (node (ref "SJ10") (pin "P$2") (pinfunction "2_P$2") (pintype "passive"))
      (node (ref "SJ11") (pin "P$2") (pinfunction "2_P$2") (pintype "passive"))
      (node (ref "SJ17") (pin "P$2") (pinfunction "2_P$2") (pintype "passive"))
      (node (ref "SJ18") (pin "P$2") (pinfunction "2_P$2") (pintype "passive"))
      (node (ref "SJ3") (pin "P$2") (pinfunction "2_P$2") (pintype "passive"))
      (node (ref "U10") (pin "6") (pinfunction "VDD_6") (pintype "power_in"))
      (node (ref "U2") (pin "1") (pinfunction "VIN_1") (pintype "bidirectional"))
      (node (ref "U5") (pin "6") (pinfunction "VDD_6") (pintype "power_in"))
      (node (ref "U6") (pin "4") (pinfunction "V+_4") (pintype "power_in"))
      (node (ref "U7") (pin "6") (pinfunction "VDD_6") (pintype "power_in"))
      (node (ref "U8") (pin "6") (pinfunction "VDD_6") (pintype "power_in"))
      (node (ref "U9") (pin "4") (pinfunction "V+_4") (pintype "power_in"))
    )
    (net (code "4") (name "/AGND") (class "Default")
      (node (ref "G1") (pin "AGND") (pinfunction "AGND_AGND") (pintype "power_in"))
    )
    (net (code "5") (name "/AVDD") (class "Default")
      (node (ref "G1") (pin "AVDD") (pinfunction "AVDD_AVDD") (pintype "power_in"))
    )
    (net (code "6") (name "/CANH") (class "Default")
      (node (ref "IC2") (pin "7") (pinfunction "CANH_7") (pintype "bidirectional"))
      (node (ref "U1") (pin "7") (pinfunction "CANH_7") (pintype "bidirectional"))
      (node (ref "X1") (pin "1") (pinfunction "1_1") (pintype "passive"))
      (node (ref "X2") (pin "1") (pinfunction "1_1") (pintype "passive"))
    )
    (net (code "7") (name "/CANL") (class "Default")
      (node (ref "IC2") (pin "6") (pinfunction "CANL_6") (pintype "bidirectional"))
      (node (ref "U1") (pin "6") (pinfunction "CANL_6") (pintype "bidirectional"))
      (node (ref "X1") (pin "2") (pinfunction "2_2") (pintype "passive"))
      (node (ref "X2") (pin "2") (pinfunction "2_2") (pintype "passive"))
    )
    (net (code "8") (name "/GND4") (class "Default")
      (node (ref "G1") (pin "GND4") (pinfunction "GND4_GND4") (pintype "power_in"))
    )
    (net (code "9") (name "/PWR_POS") (class "Default")
      (node (ref "R17") (pin "2") (pinfunction "2_2") (pintype "passive"))
      (node (ref "X1") (pin "8") (pinfunction "8_8") (pintype "passive"))
      (node (ref "X2") (pin "8") (pinfunction "8_8") (pintype "passive"))
    )
    (net (code "10") (name "/U5V") (class "Default")
      (node (ref "G1") (pin "U5V") (pinfunction "U5V_U5V") (pintype "power_in"))
    )
    (net (code "11") (name "/VBAT") (class "Default")
      (node (ref "G1") (pin "VBAT") (pinfunction "VBAT_VBAT") (pintype "power_in"))
    )
    (net (code "12") (name "/VDD") (class "Default")
      (node (ref "G1") (pin "VDD") (pinfunction "VDD_VDD") (pintype "power_in"))
    )
    (net (code "13") (name "CANRX") (class "Default")
      (node (ref "G1") (pin "PB8") (pinfunction "PB8_PB8") (pintype "bidirectional"))
      (node (ref "IC2") (pin "4") (pinfunction "RXD_4") (pintype "bidirectional"))
      (node (ref "U1") (pin "4") (pinfunction "RXD_4") (pintype "output"))
    )
    (net (code "14") (name "CANTX") (class "Default")
      (node (ref "G1") (pin "PB9") (pinfunction "PB9_PB9") (pintype "bidirectional"))
      (node (ref "IC2") (pin "1") (pinfunction "TXD_1") (pintype "bidirectional"))
      (node (ref "U1") (pin "1") (pinfunction "TXD_1") (pintype "input"))
    )
    (net (code "15") (name "E_CS") (class "Default")
      (node (ref "G1") (pin "PC10") (pinfunction "PC10_PC10") (pintype "bidirectional"))
      (node (ref "JP5") (pin "4") (pinfunction "4_4") (pintype "passive"))
      (node (ref "R1") (pin "2") (pinfunction "2_2") (pintype "passive"))
    )
    (net (code "16") (name "E_LAT") (class "Default")
      (node (ref "G1") (pin "PC11") (pinfunction "PC11_PC11") (pintype "bidirectional"))
      (node (ref "JP5") (pin "5") (pinfunction "5_5") (pintype "passive"))
      (node (ref "R2") (pin "2") (pinfunction "2_2") (pintype "passive"))
    )
    (net (code "17") (name "GND") (class "Default")
      (node (ref "C1") (pin "2") (pinfunction "2_2") (pintype "passive"))
      (node (ref "C10") (pin "2") (pinfunction "2_2") (pintype "passive"))
      (node (ref "C11") (pin "2") (pinfunction "2_2") (pintype "passive"))
      (node (ref "C2") (pin "2") (pinfunction "2_2") (pintype "passive"))
      (node (ref "C3") (pin "2") (pinfunction "2_2") (pintype "passive"))
      (node (ref "C4") (pin "2") (pinfunction "2_2") (pintype "passive"))
      (node (ref "C5") (pin "2") (pinfunction "2_2") (pintype "passive"))
      (node (ref "C6") (pin "-") (pinfunction "-_-") (pintype "passive"))
      (node (ref "C7") (pin "2") (pinfunction "2_2") (pintype "passive"))
      (node (ref "C8") (pin "2") (pinfunction "2_2") (pintype "passive"))
      (node (ref "C9") (pin "2") (pinfunction "2_2") (pintype "passive"))
      (node (ref "D5") (pin "A") (pinfunction "A_A") (pintype "passive"))
      (node (ref "D6") (pin "A") (pinfunction "A_A") (pintype "passive"))
      (node (ref "G1") (pin "GND3") (pinfunction "GND3_GND3") (pintype "power_in"))
      (node (ref "G1") (pin "GND5") (pinfunction "GND5_GND5") (pintype "power_in"))
      (node (ref "G1") (pin "GND6") (pinfunction "GND6_GND6") (pintype "power_in"))
      (node (ref "G1") (pin "GND7") (pinfunction "GND7_GND7") (pintype "power_in"))
      (node (ref "G1") (pin "GND8") (pinfunction "GND8_GND8") (pintype "power_in"))
      (node (ref "IC1") (pin "2") (pinfunction "GNDSIG_2") (pintype "input"))
      (node (ref "IC1") (pin "3") (pinfunction "~{ON/OFF}_3") (pintype "input"))
      (node (ref "IC1") (pin "4") (pinfunction "GND_4") (pintype "power_in"))
      (node (ref "IC2") (pin "2") (pinfunction "VSS_2") (pintype "power_in"))
      (node (ref "J1") (pin "2") (pinfunction "2_2") (pintype "passive"))
      (node (ref "J1") (pin "3") (pinfunction "3_3") (pintype "passive"))
      (node (ref "JP1") (pin "5") (pinfunction "5_5") (pintype "passive"))
      (node (ref "JP1") (pin "6") (pinfunction "6_6") (pintype "passive"))
      (node (ref "JP10") (pin "5") (pinfunction "5_5") (pintype "passive"))
      (node (ref "JP2") (pin "5") (pinfunction "5_5") (pintype "passive"))
      (node (ref "JP2") (pin "6") (pinfunction "6_6") (pintype "passive"))
      (node (ref "JP3") (pin "5") (pinfunction "5_5") (pintype "passive"))
      (node (ref "JP3") (pin "6") (pinfunction "6_6") (pintype "passive"))
      (node (ref "JP4") (pin "5") (pinfunction "5_5") (pintype "passive"))
      (node (ref "JP4") (pin "6") (pinfunction "6_6") (pintype "passive"))
      (node (ref "JP5") (pin "8") (pinfunction "8_8") (pintype "passive"))
      (node (ref "JP6") (pin "4") (pinfunction "4_4") (pintype "passive"))
      (node (ref "JP8") (pin "5") (pinfunction "5_5") (pintype "passive"))
      (node (ref "JP9") (pin "5") (pinfunction "5_5") (pintype "passive"))
      (node (ref "Q1") (pin "2") (pinfunction "S_2") (pintype "passive"))
      (node (ref "Q10") (pin "2") (pinfunction "S_2") (pintype "passive"))
      (node (ref "Q11") (pin "2") (pinfunction "S_2") (pintype "passive"))
      (node (ref "Q12") (pin "2") (pinfunction "S_2") (pintype "passive"))
      (node (ref "Q13") (pin "2") (pinfunction "S_2") (pintype "passive"))
      (node (ref "Q14") (pin "2") (pinfunction "S_2") (pintype "passive"))
      (node (ref "Q15") (pin "2") (pinfunction "S_2") (pintype "passive"))
      (node (ref "Q16") (pin "2") (pinfunction "S_2") (pintype "passive"))
      (node (ref "Q2") (pin "2") (pinfunction "S_2") (pintype "passive"))
      (node (ref "Q3") (pin "2") (pinfunction "S_2") (pintype "passive"))
      (node (ref "Q4") (pin "2") (pinfunction "S_2") (pintype "passive"))
      (node (ref "Q5") (pin "2") (pinfunction "S_2") (pintype "passive"))
      (node (ref "Q6") (pin "2") (pinfunction "S_2") (pintype "passive"))
      (node (ref "Q7") (pin "2") (pinfunction "S_2") (pintype "passive"))
      (node (ref "Q8") (pin "2") (pinfunction "S_2") (pintype "passive"))
      (node (ref "Q9") (pin "2") (pinfunction "S_2") (pintype "passive"))
      (node (ref "R16") (pin "2") (pinfunction "2_2") (pintype "passive"))
      (node (ref "R51") (pin "1") (pinfunction "1_1") (pintype "passive"))
      (node (ref "SJ12") (pin "2") (pinfunction "2_2") (pintype "passive"))
      (node (ref "SJ13") (pin "P$2") (pinfunction "2_P$2") (pintype "passive"))
      (node (ref "SJ19") (pin "2") (pinfunction "2_2") (pintype "passive"))
      (node (ref "SJ20") (pin "P$2") (pinfunction "2_P$2") (pintype "passive"))
      (node (ref "U1") (pin "2") (pinfunction "GND_2") (pintype "power_in"))
      (node (ref "U10") (pin "3") (pinfunction "VSS_3") (pintype "power_in"))
      (node (ref "U11") (pin "13") (pinfunction "G_13") (pintype "input"))
      (node (ref "U11") (pin "8") (pinfunction "GND_8") (pintype "power_in"))
      (node (ref "U13") (pin "13") (pinfunction "G_13") (pintype "input"))
      (node (ref "U13") (pin "8") (pinfunction "GND_8") (pintype "power_in"))
      (node (ref "U2") (pin "4") (pinfunction "SD_4") (pintype "bidirectional"))
      (node (ref "U2") (pin "5") (pinfunction "GND1_5") (pintype "power_in"))
      (node (ref "U2") (pin "6") (pinfunction "GND2_6") (pintype "power_in"))
      (node (ref "U2") (pin "7") (pinfunction "GND3_7") (pintype "power_in"))
      (node (ref "U2") (pin "8") (pinfunction "GND4_8") (pintype "power_in"))
      (node (ref "U3") (pin "6") (pinfunction "INH_6") (pintype "input"))
      (node (ref "U3") (pin "8") (pinfunction "GND_8") (pintype "power_in"))
      (node (ref "U4") (pin "6") (pinfunction "INH_6") (pintype "input"))
      (node (ref "U4") (pin "8") (pinfunction "GND_8") (pintype "power_in"))
      (node (ref "U5") (pin "3") (pinfunction "VSS_3") (pintype "power_in"))
      (node (ref "U6") (pin "11") (pinfunction "V-_11") (pintype "power_in"))
      (node (ref "U7") (pin "3") (pinfunction "VSS_3") (pintype "power_in"))
      (node (ref "U8") (pin "3") (pinfunction "VSS_3") (pintype "power_in"))
      (node (ref "U9") (pin "11") (pinfunction "V-_11") (pintype "power_in"))
      (node (ref "X1") (pin "3") (pinfunction "3_3") (pintype "passive"))
      (node (ref "X1") (pin "6") (pinfunction "6_6") (pintype "passive"))
      (node (ref "X1") (pin "7") (pinfunction "7_7") (pintype "passive"))
      (node (ref "X2") (pin "3") (pinfunction "3_3") (pintype "passive"))
      (node (ref "X2") (pin "6") (pinfunction "6_6") (pintype "passive"))
      (node (ref "X2") (pin "7") (pinfunction "7_7") (pintype "passive"))
      (node (ref "X3") (pin "2") (pinfunction "2_2") (pintype "passive"))
      (node (ref "X6") (pin "2") (pinfunction "2_2") (pintype "passive"))
    )
    (net (code "18") (name "I2CSCL") (class "Default")
      (node (ref "G1") (pin "PB6") (pinfunction "PB6_PB6") (pintype "bidirectional"))
      (node (ref "JP6") (pin "1") (pinfunction "1_1") (pintype "passive"))
      (node (ref "R15") (pin "2") (pinfunction "2_2") (pintype "passive"))
    )
    (net (code "19") (name "I2CSDA") (class "Default")
      (node (ref "G1") (pin "PB7") (pinfunction "PB7_PB7") (pintype "bidirectional"))
      (node (ref "JP6") (pin "2") (pinfunction "2_2") (pintype "passive"))
      (node (ref "R14") (pin "2") (pinfunction "2_2") (pintype "passive"))
    )
    (net (code "20") (name "ILAT") (class "Default")
      (node (ref "G1") (pin "PA6") (pinfunction "PA6_PA6") (pintype "bidirectional"))
      (node (ref "U3") (pin "15") (pinfunction "SH/~{LD}_15") (pintype "input"))
      (node (ref "U4") (pin "15") (pinfunction "SH/~{LD}_15") (pintype "input"))
    )
    (net (code "21") (name "MISO") (class "Default")
      (node (ref "G1") (pin "PB4") (pinfunction "PB4_PB4") (pintype "bidirectional"))
      (node (ref "JP5") (pin "1") (pinfunction "1_1") (pintype "passive"))
    )
    (net (code "22") (name "MISO2") (class "Default")
      (node (ref "G1") (pin "PC2") (pinfunction "PC2_PC2") (pintype "bidirectional"))
      (node (ref "SJ1") (pin "P$2") (pinfunction "2_P$2") (pintype "passive"))
      (node (ref "SJ7") (pin "P$2") (pinfunction "2_P$2") (pintype "passive"))
      (node (ref "U3") (pin "13") (pinfunction "QH_13") (pintype "output"))
    )
    (net (code "23") (name "MOSI") (class "Default")
      (node (ref "G1") (pin "PB5") (pinfunction "PB5_PB5") (pintype "bidirectional"))
      (node (ref "R4") (pin "1") (pinfunction "1_1") (pintype "passive"))
      (node (ref "SJ14") (pin "P$2") (pinfunction "2_P$2") (pintype "passive"))
      (node (ref "SJ4") (pin "1") (pinfunction "1_1") (pintype "passive"))
      (node (ref "U13") (pin "14") (pinfunction "SER_14") (pintype "input"))
    )
    (net (code "24") (name "Net-(D1-PadA)") (class "Default")
      (node (ref "D1") (pin "A") (pinfunction "A_A") (pintype "passive"))
      (node (ref "D2") (pin "A") (pinfunction "A_A") (pintype "passive"))
      (node (ref "JP7") (pin "4") (pinfunction "4_4") (pintype "passive"))
    )
    (net (code "25") (name "Net-(D1-PadC)") (class "Default")
      (node (ref "D1") (pin "C") (pinfunction "C_C") (pintype "passive"))
      (node (ref "D2") (pin "C") (pinfunction "C_C") (pintype "passive"))
      (node (ref "JP7") (pin "1") (pinfunction "1_1") (pintype "passive"))
    )
    (net (code "26") (name "Net-(D3-PadA)") (class "Default")
      (node (ref "D3") (pin "A") (pinfunction "A_A") (pintype "passive"))
      (node (ref "D4") (pin "A") (pinfunction "A_A") (pintype "passive"))
      (node (ref "J1") (pin "1") (pinfunction "1_1") (pintype "passive"))
      (node (ref "X3") (pin "1") (pinfunction "1_1") (pintype "passive"))
    )
    (net (code "27") (name "Net-(IC1-OUT)") (class "Default")
      (node (ref "D5") (pin "C") (pinfunction "C_C") (pintype "passive"))
      (node (ref "D6") (pin "C") (pinfunction "C_C") (pintype "passive"))
      (node (ref "IC1") (pin "7") (pinfunction "OUT_7") (pintype "passive"))
      (node (ref "L1") (pin "2") (pinfunction "2_2") (pintype "passive"))
      (node (ref "U2") (pin "2") (pinfunction "VOUT_2") (pintype "bidirectional"))
    )
    (net (code "28") (name "Net-(IC2-RS)") (class "Default")
      (node (ref "IC2") (pin "8") (pinfunction "RS_8") (pintype "bidirectional"))
      (node (ref "R16") (pin "1") (pinfunction "1_1") (pintype "passive"))
      (node (ref "U1") (pin "8") (pinfunction "RS_8") (pintype "input"))
    )
    (net (code "29") (name "Net-(IC2-VREF)") (class "Default")
      (node (ref "IC2") (pin "5") (pinfunction "VREF_5") (pintype "bidirectional"))
      (node (ref "SJ6") (pin "P$2") (pinfunction "2_P$2") (pintype "passive"))
      (node (ref "U1") (pin "5") (pinfunction "VREF_5") (pintype "output"))
    )
    (net (code "30") (name "Net-(JP7-Pad3)") (class "Default")
      (node (ref "JP7") (pin "3") (pinfunction "3_3") (pintype "passive"))
      (node (ref "R17") (pin "1") (pinfunction "1_1") (pintype "passive"))
    )
    (net (code "31") (name "Net-(JP8-Pad10)") (class "Default")
      (node (ref "JP8") (pin "10") (pinfunction "10_10") (pintype "passive"))
      (node (ref "R25") (pin "2") (pinfunction "2_2") (pintype "passive"))
      (node (ref "R26") (pin "2") (pinfunction "2_2") (pintype "passive"))
      (node (ref "RN1") (pin "9") (pinfunction "9_9") (pintype "passive"))
      (node (ref "RN2") (pin "1") (pinfunction "1_1") (pintype "passive"))
      (node (ref "X4") (pin "1") (pinfunction "1_1") (pintype "passive"))
    )
    (net (code "32") (name "Net-(JP9-Pad10)") (class "Default")
      (node (ref "JP9") (pin "10") (pinfunction "10_10") (pintype "passive"))
      (node (ref "R41") (pin "2") (pinfunction "2_2") (pintype "passive"))
      (node (ref "R42") (pin "2") (pinfunction "2_2") (pintype "passive"))
      (node (ref "RN3") (pin "9") (pinfunction "9_9") (pintype "passive"))
      (node (ref "RN4") (pin "1") (pinfunction "1_1") (pintype "passive"))
      (node (ref "X5") (pin "1") (pinfunction "1_1") (pintype "passive"))
    )
    (net (code "33") (name "Net-(Q1-D)") (class "Default")
      (node (ref "Q1") (pin "3") (pinfunction "D_3") (pintype "passive"))
      (node (ref "U12") (pin "11") (pinfunction "O8_11") (pintype "open_collector"))
      (node (ref "X8") (pin "8") (pinfunction "8_8") (pintype "passive"))
    )
    (net (code "34") (name "Net-(Q1-G)") (class "Default")
      (node (ref "Q1") (pin "1") (pinfunction "G_1") (pintype "passive"))
      (node (ref "R52") (pin "2") (pinfunction "2_2") (pintype "passive"))
    )
    (net (code "35") (name "Net-(Q2-D)") (class "Default")
      (node (ref "Q2") (pin "3") (pinfunction "D_3") (pintype "passive"))
      (node (ref "U12") (pin "12") (pinfunction "O7_12") (pintype "open_collector"))
      (node (ref "X8") (pin "7") (pinfunction "7_7") (pintype "passive"))
    )
    (net (code "36") (name "Net-(Q2-G)") (class "Default")
      (node (ref "Q2") (pin "1") (pinfunction "G_1") (pintype "passive"))
      (node (ref "R53") (pin "2") (pinfunction "2_2") (pintype "passive"))
    )
    (net (code "37") (name "Net-(Q3-D)") (class "Default")
      (node (ref "Q3") (pin "3") (pinfunction "D_3") (pintype "passive"))
      (node (ref "U12") (pin "13") (pinfunction "O6_13") (pintype "open_collector"))
      (node (ref "X8") (pin "6") (pinfunction "6_6") (pintype "passive"))
    )
    (net (code "38") (name "Net-(Q3-G)") (class "Default")
      (node (ref "Q3") (pin "1") (pinfunction "G_1") (pintype "passive"))
      (node (ref "R54") (pin "2") (pinfunction "2_2") (pintype "passive"))
    )
    (net (code "39") (name "Net-(Q4-D)") (class "Default")
      (node (ref "Q4") (pin "3") (pinfunction "D_3") (pintype "passive"))
      (node (ref "U12") (pin "14") (pinfunction "O5_14") (pintype "open_collector"))
      (node (ref "X8") (pin "5") (pinfunction "5_5") (pintype "passive"))
    )
    (net (code "40") (name "Net-(Q4-G)") (class "Default")
      (node (ref "Q4") (pin "1") (pinfunction "G_1") (pintype "passive"))
      (node (ref "R55") (pin "2") (pinfunction "2_2") (pintype "passive"))
    )
    (net (code "41") (name "Net-(Q5-D)") (class "Default")
      (node (ref "Q5") (pin "3") (pinfunction "D_3") (pintype "passive"))
      (node (ref "U12") (pin "15") (pinfunction "O4_15") (pintype "open_collector"))
      (node (ref "X8") (pin "4") (pinfunction "4_4") (pintype "passive"))
    )
    (net (code "42") (name "Net-(Q5-G)") (class "Default")
      (node (ref "Q5") (pin "1") (pinfunction "G_1") (pintype "passive"))
      (node (ref "R56") (pin "2") (pinfunction "2_2") (pintype "passive"))
    )
    (net (code "43") (name "Net-(Q6-D)") (class "Default")
      (node (ref "Q6") (pin "3") (pinfunction "D_3") (pintype "passive"))
      (node (ref "U12") (pin "16") (pinfunction "O3_16") (pintype "open_collector"))
      (node (ref "X8") (pin "3") (pinfunction "3_3") (pintype "passive"))
    )
    (net (code "44") (name "Net-(Q6-G)") (class "Default")
      (node (ref "Q6") (pin "1") (pinfunction "G_1") (pintype "passive"))
      (node (ref "R57") (pin "2") (pinfunction "2_2") (pintype "passive"))
    )
    (net (code "45") (name "Net-(Q7-D)") (class "Default")
      (node (ref "Q7") (pin "3") (pinfunction "D_3") (pintype "passive"))
      (node (ref "U12") (pin "17") (pinfunction "O2_17") (pintype "open_collector"))
      (node (ref "X8") (pin "2") (pinfunction "2_2") (pintype "passive"))
    )
    (net (code "46") (name "Net-(Q7-G)") (class "Default")
      (node (ref "Q7") (pin "1") (pinfunction "G_1") (pintype "passive"))
      (node (ref "R58") (pin "2") (pinfunction "2_2") (pintype "passive"))
    )
    (net (code "47") (name "Net-(Q8-D)") (class "Default")
      (node (ref "Q8") (pin "3") (pinfunction "D_3") (pintype "passive"))
      (node (ref "U12") (pin "18") (pinfunction "O1_18") (pintype "open_collector"))
      (node (ref "X8") (pin "1") (pinfunction "1_1") (pintype "passive"))
    )
    (net (code "48") (name "Net-(Q8-G)") (class "Default")
      (node (ref "Q8") (pin "1") (pinfunction "G_1") (pintype "passive"))
      (node (ref "R59") (pin "2") (pinfunction "2_2") (pintype "passive"))
    )
    (net (code "49") (name "Net-(Q9-D)") (class "Default")
      (node (ref "Q9") (pin "3") (pinfunction "D_3") (pintype "passive"))
      (node (ref "U14") (pin "11") (pinfunction "O8_11") (pintype "open_collector"))
      (node (ref "X9") (pin "8") (pinfunction "8_8") (pintype "passive"))
    )
    (net (code "50") (name "Net-(Q9-G)") (class "Default")
      (node (ref "Q9") (pin "1") (pinfunction "G_1") (pintype "passive"))
      (node (ref "R60") (pin "2") (pinfunction "2_2") (pintype "passive"))
    )
    (net (code "51") (name "Net-(Q10-D)") (class "Default")
      (node (ref "Q10") (pin "3") (pinfunction "D_3") (pintype "passive"))
      (node (ref "U14") (pin "12") (pinfunction "O7_12") (pintype "open_collector"))
      (node (ref "X9") (pin "7") (pinfunction "7_7") (pintype "passive"))
    )
    (net (code "52") (name "Net-(Q10-G)") (class "Default")
      (node (ref "Q10") (pin "1") (pinfunction "G_1") (pintype "passive"))
      (node (ref "R61") (pin "2") (pinfunction "2_2") (pintype "passive"))
    )
    (net (code "53") (name "Net-(Q11-D)") (class "Default")
      (node (ref "Q11") (pin "3") (pinfunction "D_3") (pintype "passive"))
      (node (ref "U14") (pin "13") (pinfunction "O6_13") (pintype "open_collector"))
      (node (ref "X9") (pin "6") (pinfunction "6_6") (pintype "passive"))
    )
    (net (code "54") (name "Net-(Q11-G)") (class "Default")
      (node (ref "Q11") (pin "1") (pinfunction "G_1") (pintype "passive"))
      (node (ref "R62") (pin "2") (pinfunction "2_2") (pintype "passive"))
    )
    (net (code "55") (name "Net-(Q12-D)") (class "Default")
      (node (ref "Q12") (pin "3") (pinfunction "D_3") (pintype "passive"))
      (node (ref "U14") (pin "14") (pinfunction "O5_14") (pintype "open_collector"))
      (node (ref "X9") (pin "5") (pinfunction "5_5") (pintype "passive"))
    )
    (net (code "56") (name "Net-(Q12-G)") (class "Default")
      (node (ref "Q12") (pin "1") (pinfunction "G_1") (pintype "passive"))
      (node (ref "R63") (pin "2") (pinfunction "2_2") (pintype "passive"))
    )
    (net (code "57") (name "Net-(Q13-D)") (class "Default")
      (node (ref "Q13") (pin "3") (pinfunction "D_3") (pintype "passive"))
      (node (ref "U14") (pin "15") (pinfunction "O4_15") (pintype "open_collector"))
      (node (ref "X9") (pin "4") (pinfunction "4_4") (pintype "passive"))
    )
    (net (code "58") (name "Net-(Q13-G)") (class "Default")
      (node (ref "Q13") (pin "1") (pinfunction "G_1") (pintype "passive"))
      (node (ref "R64") (pin "2") (pinfunction "2_2") (pintype "passive"))
    )
    (net (code "59") (name "Net-(Q14-D)") (class "Default")
      (node (ref "Q14") (pin "3") (pinfunction "D_3") (pintype "passive"))
      (node (ref "U14") (pin "16") (pinfunction "O3_16") (pintype "open_collector"))
      (node (ref "X9") (pin "3") (pinfunction "3_3") (pintype "passive"))
    )
    (net (code "60") (name "Net-(Q14-G)") (class "Default")
      (node (ref "Q14") (pin "1") (pinfunction "G_1") (pintype "passive"))
      (node (ref "R65") (pin "2") (pinfunction "2_2") (pintype "passive"))
    )
    (net (code "61") (name "Net-(Q15-D)") (class "Default")
      (node (ref "Q15") (pin "3") (pinfunction "D_3") (pintype "passive"))
      (node (ref "U14") (pin "17") (pinfunction "O2_17") (pintype "open_collector"))
      (node (ref "X9") (pin "2") (pinfunction "2_2") (pintype "passive"))
    )
    (net (code "62") (name "Net-(Q15-G)") (class "Default")
      (node (ref "Q15") (pin "1") (pinfunction "G_1") (pintype "passive"))
      (node (ref "R66") (pin "2") (pinfunction "2_2") (pintype "passive"))
    )
    (net (code "63") (name "Net-(Q16-D)") (class "Default")
      (node (ref "Q16") (pin "3") (pinfunction "D_3") (pintype "passive"))
      (node (ref "U14") (pin "18") (pinfunction "O1_18") (pintype "open_collector"))
      (node (ref "X9") (pin "1") (pinfunction "1_1") (pintype "passive"))
    )
    (net (code "64") (name "Net-(Q16-G)") (class "Default")
      (node (ref "Q16") (pin "1") (pinfunction "G_1") (pintype "passive"))
      (node (ref "R67") (pin "2") (pinfunction "2_2") (pintype "passive"))
    )
    (net (code "65") (name "Net-(RN2A-2)") (class "Default")
      (node (ref "R25") (pin "1") (pinfunction "1_1") (pintype "passive"))
      (node (ref "RN2") (pin "16") (pinfunction "2_16") (pintype "passive"))
      (node (ref "U3") (pin "14") (pinfunction "H_14") (pintype "input"))
    )
    (net (code "66") (name "Net-(RN2B-1)") (class "Default")
      (node (ref "JP8") (pin "9") (pinfunction "9_9") (pintype "passive"))
      (node (ref "R24") (pin "2") (pinfunction "2_2") (pintype "passive"))
      (node (ref "R27") (pin "2") (pinfunction "2_2") (pintype "passive"))
      (node (ref "RN1") (pin "8") (pinfunction "8_8") (pintype "passive"))
      (node (ref "RN2") (pin "2") (pinfunction "1_2") (pintype "passive"))
      (node (ref "X4") (pin "2") (pinfunction "2_2") (pintype "passive"))
    )
    (net (code "67") (name "Net-(RN2B-2)") (class "Default")
      (node (ref "R24") (pin "1") (pinfunction "1_1") (pintype "passive"))
      (node (ref "RN2") (pin "15") (pinfunction "2_15") (pintype "passive"))
      (node (ref "U3") (pin "12") (pinfunction "G_12") (pintype "input"))
    )
    (net (code "68") (name "Net-(RN2C-1)") (class "Default")
      (node (ref "JP8") (pin "8") (pinfunction "8_8") (pintype "passive"))
      (node (ref "R23") (pin "2") (pinfunction "2_2") (pintype "passive"))
      (node (ref "R28") (pin "2") (pinfunction "2_2") (pintype "passive"))
      (node (ref "RN1") (pin "7") (pinfunction "7_7") (pintype "passive"))
      (node (ref "RN2") (pin "3") (pinfunction "1_3") (pintype "passive"))
      (node (ref "X4") (pin "3") (pinfunction "3_3") (pintype "passive"))
    )
    (net (code "69") (name "Net-(RN2C-2)") (class "Default")
      (node (ref "R23") (pin "1") (pinfunction "1_1") (pintype "passive"))
      (node (ref "RN2") (pin "14") (pinfunction "2_14") (pintype "passive"))
      (node (ref "U3") (pin "11") (pinfunction "F_11") (pintype "input"))
    )
    (net (code "70") (name "Net-(RN2D-1)") (class "Default")
      (node (ref "JP8") (pin "7") (pinfunction "7_7") (pintype "passive"))
      (node (ref "R22") (pin "2") (pinfunction "2_2") (pintype "passive"))
      (node (ref "R29") (pin "2") (pinfunction "2_2") (pintype "passive"))
      (node (ref "RN1") (pin "6") (pinfunction "6_6") (pintype "passive"))
      (node (ref "RN2") (pin "4") (pinfunction "1_4") (pintype "passive"))
      (node (ref "X4") (pin "4") (pinfunction "4_4") (pintype "passive"))
    )
    (net (code "71") (name "Net-(RN2D-2)") (class "Default")
      (node (ref "R22") (pin "1") (pinfunction "1_1") (pintype "passive"))
      (node (ref "RN2") (pin "13") (pinfunction "2_13") (pintype "passive"))
      (node (ref "U3") (pin "10") (pinfunction "E_10") (pintype "input"))
    )
    (net (code "72") (name "Net-(RN2E-1)") (class "Default")
      (node (ref "JP8") (pin "4") (pinfunction "4_4") (pintype "passive"))
      (node (ref "R21") (pin "2") (pinfunction "2_2") (pintype "passive"))
      (node (ref "R30") (pin "2") (pinfunction "2_2") (pintype "passive"))
      (node (ref "RN1") (pin "5") (pinfunction "5_5") (pintype "passive"))
      (node (ref "RN2") (pin "5") (pinfunction "1_5") (pintype "passive"))
      (node (ref "X4") (pin "5") (pinfunction "5_5") (pintype "passive"))
    )
    (net (code "73") (name "Net-(RN2E-2)") (class "Default")
      (node (ref "R21") (pin "1") (pinfunction "1_1") (pintype "passive"))
      (node (ref "RN2") (pin "12") (pinfunction "2_12") (pintype "passive"))
      (node (ref "U3") (pin "5") (pinfunction "D_5") (pintype "input"))
    )
    (net (code "74") (name "Net-(RN2F-1)") (class "Default")
      (node (ref "JP8") (pin "3") (pinfunction "3_3") (pintype "passive"))
      (node (ref "R20") (pin "2") (pinfunction "2_2") (pintype "passive"))
      (node (ref "R31") (pin "2") (pinfunction "2_2") (pintype "passive"))
      (node (ref "RN1") (pin "4") (pinfunction "4_4") (pintype "passive"))
      (node (ref "RN2") (pin "6") (pinfunction "1_6") (pintype "passive"))
      (node (ref "X4") (pin "6") (pinfunction "6_6") (pintype "passive"))
    )
    (net (code "75") (name "Net-(RN2F-2)") (class "Default")
      (node (ref "R20") (pin "1") (pinfunction "1_1") (pintype "passive"))
      (node (ref "RN2") (pin "11") (pinfunction "2_11") (pintype "passive"))
      (node (ref "U3") (pin "4") (pinfunction "C_4") (pintype "input"))
    )
    (net (code "76") (name "Net-(RN2G-1)") (class "Default")
      (node (ref "JP8") (pin "2") (pinfunction "2_2") (pintype "passive"))
      (node (ref "R19") (pin "2") (pinfunction "2_2") (pintype "passive"))
      (node (ref "R32") (pin "2") (pinfunction "2_2") (pintype "passive"))
      (node (ref "RN1") (pin "3") (pinfunction "3_3") (pintype "passive"))
      (node (ref "RN2") (pin "7") (pinfunction "1_7") (pintype "passive"))
      (node (ref "X4") (pin "7") (pinfunction "7_7") (pintype "passive"))
    )
    (net (code "77") (name "Net-(RN2G-2)") (class "Default")
      (node (ref "R19") (pin "1") (pinfunction "1_1") (pintype "passive"))
      (node (ref "RN2") (pin "10") (pinfunction "2_10") (pintype "passive"))
      (node (ref "U3") (pin "3") (pinfunction "B_3") (pintype "input"))
    )
    (net (code "78") (name "Net-(RN2H-1)") (class "Default")
      (node (ref "JP8") (pin "1") (pinfunction "1_1") (pintype "passive"))
      (node (ref "R18") (pin "2") (pinfunction "2_2") (pintype "passive"))
      (node (ref "R33") (pin "2") (pinfunction "2_2") (pintype "passive"))
      (node (ref "RN1") (pin "2") (pinfunction "2_2") (pintype "passive"))
      (node (ref "RN2") (pin "8") (pinfunction "1_8") (pintype "passive"))
      (node (ref "X4") (pin "8") (pinfunction "8_8") (pintype "passive"))
    )
    (net (code "79") (name "Net-(RN2H-2)") (class "Default")
      (node (ref "R18") (pin "1") (pinfunction "1_1") (pintype "passive"))
      (node (ref "RN2") (pin "9") (pinfunction "2_9") (pintype "passive"))
      (node (ref "U3") (pin "2") (pinfunction "A_2") (pintype "input"))
    )
    (net (code "80") (name "Net-(RN4A-2)") (class "Default")
      (node (ref "R41") (pin "1") (pinfunction "1_1") (pintype "passive"))
      (node (ref "RN4") (pin "16") (pinfunction "2_16") (pintype "passive"))
      (node (ref "U4") (pin "14") (pinfunction "H_14") (pintype "input"))
    )
    (net (code "81") (name "Net-(RN4B-1)") (class "Default")
      (node (ref "JP9") (pin "9") (pinfunction "9_9") (pintype "passive"))
      (node (ref "R40") (pin "2") (pinfunction "2_2") (pintype "passive"))
      (node (ref "R43") (pin "2") (pinfunction "2_2") (pintype "passive"))
      (node (ref "RN3") (pin "8") (pinfunction "8_8") (pintype "passive"))
      (node (ref "RN4") (pin "2") (pinfunction "1_2") (pintype "passive"))
      (node (ref "X5") (pin "2") (pinfunction "2_2") (pintype "passive"))
    )
    (net (code "82") (name "Net-(RN4B-2)") (class "Default")
      (node (ref "R40") (pin "1") (pinfunction "1_1") (pintype "passive"))
      (node (ref "RN4") (pin "15") (pinfunction "2_15") (pintype "passive"))
      (node (ref "U4") (pin "12") (pinfunction "G_12") (pintype "input"))
    )
    (net (code "83") (name "Net-(RN4C-1)") (class "Default")
      (node (ref "JP9") (pin "8") (pinfunction "8_8") (pintype "passive"))
      (node (ref "R39") (pin "2") (pinfunction "2_2") (pintype "passive"))
      (node (ref "R44") (pin "2") (pinfunction "2_2") (pintype "passive"))
      (node (ref "RN3") (pin "7") (pinfunction "7_7") (pintype "passive"))
      (node (ref "RN4") (pin "3") (pinfunction "1_3") (pintype "passive"))
      (node (ref "X5") (pin "3") (pinfunction "3_3") (pintype "passive"))
    )
    (net (code "84") (name "Net-(RN4C-2)") (class "Default")
      (node (ref "R39") (pin "1") (pinfunction "1_1") (pintype "passive"))
      (node (ref "RN4") (pin "14") (pinfunction "2_14") (pintype "passive"))
      (node (ref "U4") (pin "11") (pinfunction "F_11") (pintype "input"))
    )
    (net (code "85") (name "Net-(RN4D-1)") (class "Default")
      (node (ref "JP9") (pin "7") (pinfunction "7_7") (pintype "passive"))
      (node (ref "R38") (pin "2") (pinfunction "2_2") (pintype "passive"))
      (node (ref "R45") (pin "2") (pinfunction "2_2") (pintype "passive"))
      (node (ref "RN3") (pin "6") (pinfunction "6_6") (pintype "passive"))
      (node (ref "RN4") (pin "4") (pinfunction "1_4") (pintype "passive"))
      (node (ref "X5") (pin "4") (pinfunction "4_4") (pintype "passive"))
    )
    (net (code "86") (name "Net-(RN4D-2)") (class "Default")
      (node (ref "R38") (pin "1") (pinfunction "1_1") (pintype "passive"))
      (node (ref "RN4") (pin "13") (pinfunction "2_13") (pintype "passive"))
      (node (ref "U4") (pin "10") (pinfunction "E_10") (pintype "input"))
    )
    (net (code "87") (name "Net-(RN4E-1)") (class "Default")
      (node (ref "JP9") (pin "4") (pinfunction "4_4") (pintype "passive"))
      (node (ref "R37") (pin "2") (pinfunction "2_2") (pintype "passive"))
      (node (ref "R46") (pin "2") (pinfunction "2_2") (pintype "passive"))
      (node (ref "RN3") (pin "5") (pinfunction "5_5") (pintype "passive"))
      (node (ref "RN4") (pin "5") (pinfunction "1_5") (pintype "passive"))
      (node (ref "X5") (pin "5") (pinfunction "5_5") (pintype "passive"))
    )
    (net (code "88") (name "Net-(RN4E-2)") (class "Default")
      (node (ref "R37") (pin "1") (pinfunction "1_1") (pintype "passive"))
      (node (ref "RN4") (pin "12") (pinfunction "2_12") (pintype "passive"))
      (node (ref "U4") (pin "5") (pinfunction "D_5") (pintype "input"))
    )
    (net (code "89") (name "Net-(RN4F-1)") (class "Default")
      (node (ref "JP9") (pin "3") (pinfunction "3_3") (pintype "passive"))
      (node (ref "R36") (pin "2") (pinfunction "2_2") (pintype "passive"))
      (node (ref "R47") (pin "2") (pinfunction "2_2") (pintype "passive"))
      (node (ref "RN3") (pin "4") (pinfunction "4_4") (pintype "passive"))
      (node (ref "RN4") (pin "6") (pinfunction "1_6") (pintype "passive"))
      (node (ref "X5") (pin "6") (pinfunction "6_6") (pintype "passive"))
    )
    (net (code "90") (name "Net-(RN4F-2)") (class "Default")
      (node (ref "R36") (pin "1") (pinfunction "1_1") (pintype "passive"))
      (node (ref "RN4") (pin "11") (pinfunction "2_11") (pintype "passive"))
      (node (ref "U4") (pin "4") (pinfunction "C_4") (pintype "input"))
    )
    (net (code "91") (name "Net-(RN4G-1)") (class "Default")
      (node (ref "JP9") (pin "2") (pinfunction "2_2") (pintype "passive"))
      (node (ref "R35") (pin "2") (pinfunction "2_2") (pintype "passive"))
      (node (ref "R48") (pin "2") (pinfunction "2_2") (pintype "passive"))
      (node (ref "RN3") (pin "3") (pinfunction "3_3") (pintype "passive"))
      (node (ref "RN4") (pin "7") (pinfunction "1_7") (pintype "passive"))
      (node (ref "X5") (pin "7") (pinfunction "7_7") (pintype "passive"))
    )
    (net (code "92") (name "Net-(RN4G-2)") (class "Default")
      (node (ref "R35") (pin "1") (pinfunction "1_1") (pintype "passive"))
      (node (ref "RN4") (pin "10") (pinfunction "2_10") (pintype "passive"))
      (node (ref "U4") (pin "3") (pinfunction "B_3") (pintype "input"))
    )
    (net (code "93") (name "Net-(RN4H-1)") (class "Default")
      (node (ref "JP9") (pin "1") (pinfunction "1_1") (pintype "passive"))
      (node (ref "R34") (pin "2") (pinfunction "2_2") (pintype "passive"))
      (node (ref "R49") (pin "2") (pinfunction "2_2") (pintype "passive"))
      (node (ref "RN3") (pin "2") (pinfunction "2_2") (pintype "passive"))
      (node (ref "RN4") (pin "8") (pinfunction "1_8") (pintype "passive"))
      (node (ref "X5") (pin "8") (pinfunction "8_8") (pintype "passive"))
    )
    (net (code "94") (name "Net-(RN4H-2)") (class "Default")
      (node (ref "R34") (pin "1") (pinfunction "1_1") (pintype "passive"))
      (node (ref "RN4") (pin "9") (pinfunction "2_9") (pintype "passive"))
      (node (ref "U4") (pin "2") (pinfunction "A_2") (pintype "input"))
    )
    (net (code "95") (name "Net-(SJ1-1)") (class "Default")
      (node (ref "G1") (pin "PB14") (pinfunction "PB14_PB14") (pintype "bidirectional"))
      (node (ref "SJ1") (pin "P$1") (pinfunction "1_P$1") (pintype "passive"))
    )
    (net (code "96") (name "Net-(SJ2-2)") (class "Default")
      (node (ref "G1") (pin "PB13") (pinfunction "PB13_PB13") (pintype "bidirectional"))
      (node (ref "SJ2") (pin "P$2") (pinfunction "2_P$2") (pintype "passive"))
    )
    (net (code "97") (name "Net-(SJ3-1)") (class "Default")
      (node (ref "G1") (pin "VIN2") (pinfunction "VIN2_VIN2") (pintype "power_in"))
      (node (ref "SJ3") (pin "P$1") (pinfunction "1_P$1") (pintype "passive"))
    )
    (net (code "98") (name "Net-(SJ5-2)") (class "Default")
      (node (ref "JP5") (pin "2") (pinfunction "2_2") (pintype "passive"))
      (node (ref "SJ4") (pin "2") (pinfunction "2_2") (pintype "passive"))
      (node (ref "SJ5") (pin "P$2") (pinfunction "2_P$2") (pintype "passive"))
    )
    (net (code "99") (name "Net-(SJ10-1)") (class "Default")
      (node (ref "SJ10") (pin "P$1") (pinfunction "1_P$1") (pintype "passive"))
      (node (ref "SJ12") (pin "1") (pinfunction "1_1") (pintype "passive"))
      (node (ref "SJ8") (pin "P$1") (pinfunction "1_P$1") (pintype "passive"))
      (node (ref "U12") (pin "9") (pinfunction "GND_9") (pintype "power_in"))
    )
    (net (code "100") (name "Net-(SJ11-1)") (class "Default")
      (node (ref "SJ11") (pin "P$1") (pinfunction "1_P$1") (pintype "passive"))
      (node (ref "SJ13") (pin "P$1") (pinfunction "1_P$1") (pintype "passive"))
      (node (ref "SJ9") (pin "P$1") (pinfunction "1_P$1") (pintype "passive"))
      (node (ref "U12") (pin "10") (pinfunction "CD+_10") (pintype "passive"))
      (node (ref "X8") (pin "9") (pinfunction "9_9") (pintype "passive"))
    )
    (net (code "101") (name "Net-(SJ15-1)") (class "Default")
      (node (ref "SJ15") (pin "P$1") (pinfunction "1_P$1") (pintype "passive"))
      (node (ref "SJ17") (pin "P$1") (pinfunction "1_P$1") (pintype "passive"))
      (node (ref "SJ19") (pin "1") (pinfunction "1_1") (pintype "passive"))
      (node (ref "U14") (pin "9") (pinfunction "GND_9") (pintype "power_in"))
    )
    (net (code "102") (name "Net-(SJ16-1)") (class "Default")
      (node (ref "SJ16") (pin "P$1") (pinfunction "1_P$1") (pintype "passive"))
      (node (ref "SJ18") (pin "P$1") (pinfunction "1_P$1") (pintype "passive"))
      (node (ref "SJ20") (pin "P$1") (pinfunction "1_P$1") (pintype "passive"))
      (node (ref "U14") (pin "10") (pinfunction "CD+_10") (pintype "passive"))
      (node (ref "X9") (pin "9") (pinfunction "9_9") (pintype "passive"))
    )
    (net (code "103") (name "Net-(U5A-O)") (class "Default")
      (node (ref "JP10") (pin "1") (pinfunction "1_1") (pintype "passive"))
      (node (ref "U5") (pin "7") (pinfunction "O_7") (pintype "output"))
      (node (ref "U6") (pin "7") (pinfunction "OUT_7") (pintype "output"))
      (node (ref "X7") (pin "1") (pinfunction "1_1") (pintype "passive"))
    )
    (net (code "104") (name "Net-(U5B-O)") (class "Default")
      (node (ref "JP10") (pin "2") (pinfunction "2_2") (pintype "passive"))
      (node (ref "U5") (pin "5") (pinfunction "O_5") (pintype "output"))
      (node (ref "U6") (pin "8") (pinfunction "OUT_8") (pintype "output"))
      (node (ref "X7") (pin "2") (pinfunction "2_2") (pintype "passive"))
    )
    (net (code "105") (name "Net-(U6A--IN)") (class "Default")
      (node (ref "R50") (pin "1") (pinfunction "1_1") (pintype "passive"))
      (node (ref "R51") (pin "2") (pinfunction "2_2") (pintype "passive"))
      (node (ref "U6") (pin "13") (pinfunction "-IN_13") (pintype "input"))
      (node (ref "U6") (pin "2") (pinfunction "-IN_2") (pintype "input"))
      (node (ref "U6") (pin "6") (pinfunction "-IN_6") (pintype "input"))
      (node (ref "U6") (pin "9") (pinfunction "-IN_9") (pintype "input"))
      (node (ref "U9") (pin "13") (pinfunction "-IN_13") (pintype "input"))
      (node (ref "U9") (pin "2") (pinfunction "-IN_2") (pintype "input"))
      (node (ref "U9") (pin "6") (pinfunction "-IN_6") (pintype "input"))
      (node (ref "U9") (pin "9") (pinfunction "-IN_9") (pintype "input"))
    )
    (net (code "106") (name "Net-(U6A-OUT)") (class "Default")
      (node (ref "JP10") (pin "3") (pinfunction "3_3") (pintype "passive"))
      (node (ref "U6") (pin "1") (pinfunction "OUT_1") (pintype "output"))
      (node (ref "U7") (pin "5") (pinfunction "O_5") (pintype "output"))
      (node (ref "X7") (pin "3") (pinfunction "3_3") (pintype "passive"))
    )
    (net (code "107") (name "Net-(U6D-OUT)") (class "Default")
      (node (ref "JP10") (pin "4") (pinfunction "4_4") (pintype "passive"))
      (node (ref "U6") (pin "14") (pinfunction "OUT_14") (pintype "output"))
      (node (ref "U7") (pin "7") (pinfunction "O_7") (pintype "output"))
      (node (ref "X7") (pin "4") (pinfunction "4_4") (pintype "passive"))
    )
    (net (code "108") (name "Net-(U8A-O)") (class "Default")
      (node (ref "JP10") (pin "7") (pinfunction "7_7") (pintype "passive"))
      (node (ref "U8") (pin "7") (pinfunction "O_7") (pintype "output"))
      (node (ref "U9") (pin "7") (pinfunction "OUT_7") (pintype "output"))
      (node (ref "X7") (pin "5") (pinfunction "5_5") (pintype "passive"))
    )
    (net (code "109") (name "Net-(U8B-O)") (class "Default")
      (node (ref "JP10") (pin "8") (pinfunction "8_8") (pintype "passive"))
      (node (ref "U8") (pin "5") (pinfunction "O_5") (pintype "output"))
      (node (ref "U9") (pin "8") (pinfunction "OUT_8") (pintype "output"))
      (node (ref "X7") (pin "6") (pinfunction "6_6") (pintype "passive"))
    )
    (net (code "110") (name "Net-(U10A-O)") (class "Default")
      (node (ref "JP10") (pin "10") (pinfunction "10_10") (pintype "passive"))
      (node (ref "U10") (pin "7") (pinfunction "O_7") (pintype "output"))
      (node (ref "U9") (pin "14") (pinfunction "OUT_14") (pintype "output"))
      (node (ref "X7") (pin "8") (pinfunction "8_8") (pintype "passive"))
    )
    (net (code "111") (name "Net-(U10B-O)") (class "Default")
      (node (ref "JP10") (pin "9") (pinfunction "9_9") (pintype "passive"))
      (node (ref "U10") (pin "5") (pinfunction "O_5") (pintype "output"))
      (node (ref "U9") (pin "1") (pinfunction "OUT_1") (pintype "output"))
      (node (ref "X7") (pin "7") (pinfunction "7_7") (pintype "passive"))
    )
    (net (code "112") (name "Net-(U11A-QA)") (class "Default")
      (node (ref "R59") (pin "1") (pinfunction "1_1") (pintype "passive"))
      (node (ref "U11") (pin "15") (pinfunction "QA_15") (pintype "tri_state"))
      (node (ref "U12") (pin "1") (pinfunction "I1_1") (pintype "input"))
    )
    (net (code "113") (name "Net-(U11A-QB)") (class "Default")
      (node (ref "R58") (pin "1") (pinfunction "1_1") (pintype "passive"))
      (node (ref "U11") (pin "1") (pinfunction "QB_1") (pintype "tri_state"))
      (node (ref "U12") (pin "2") (pinfunction "I2_2") (pintype "input"))
    )
    (net (code "114") (name "Net-(U11A-QC)") (class "Default")
      (node (ref "R57") (pin "1") (pinfunction "1_1") (pintype "passive"))
      (node (ref "U11") (pin "2") (pinfunction "QC_2") (pintype "tri_state"))
      (node (ref "U12") (pin "3") (pinfunction "I3_3") (pintype "input"))
    )
    (net (code "115") (name "Net-(U11A-QD)") (class "Default")
      (node (ref "R56") (pin "1") (pinfunction "1_1") (pintype "passive"))
      (node (ref "U11") (pin "3") (pinfunction "QD_3") (pintype "tri_state"))
      (node (ref "U12") (pin "4") (pinfunction "I4_4") (pintype "input"))
    )
    (net (code "116") (name "Net-(U11A-QE)") (class "Default")
      (node (ref "R55") (pin "1") (pinfunction "1_1") (pintype "passive"))
      (node (ref "U11") (pin "4") (pinfunction "QE_4") (pintype "tri_state"))
      (node (ref "U12") (pin "5") (pinfunction "I5_5") (pintype "input"))
    )
    (net (code "117") (name "Net-(U11A-QF)") (class "Default")
      (node (ref "R54") (pin "1") (pinfunction "1_1") (pintype "passive"))
      (node (ref "U11") (pin "5") (pinfunction "QF_5") (pintype "tri_state"))
      (node (ref "U12") (pin "6") (pinfunction "I6_6") (pintype "input"))
    )
    (net (code "118") (name "Net-(U11A-QG)") (class "Default")
      (node (ref "R53") (pin "1") (pinfunction "1_1") (pintype "passive"))
      (node (ref "U11") (pin "6") (pinfunction "QG_6") (pintype "tri_state"))
      (node (ref "U12") (pin "7") (pinfunction "I7_7") (pintype "input"))
    )
    (net (code "119") (name "Net-(U11A-QH)") (class "Default")
      (node (ref "R52") (pin "1") (pinfunction "1_1") (pintype "passive"))
      (node (ref "U11") (pin "7") (pinfunction "QH_7") (pintype "tri_state"))
      (node (ref "U12") (pin "8") (pinfunction "I8_8") (pintype "input"))
    )
    (net (code "120") (name "Net-(U13A-QA)") (class "Default")
      (node (ref "R67") (pin "1") (pinfunction "1_1") (pintype "passive"))
      (node (ref "U13") (pin "15") (pinfunction "QA_15") (pintype "tri_state"))
      (node (ref "U14") (pin "1") (pinfunction "I1_1") (pintype "input"))
    )
    (net (code "121") (name "Net-(U13A-QB)") (class "Default")
      (node (ref "R66") (pin "1") (pinfunction "1_1") (pintype "passive"))
      (node (ref "U13") (pin "1") (pinfunction "QB_1") (pintype "tri_state"))
      (node (ref "U14") (pin "2") (pinfunction "I2_2") (pintype "input"))
    )
    (net (code "122") (name "Net-(U13A-QC)") (class "Default")
      (node (ref "R65") (pin "1") (pinfunction "1_1") (pintype "passive"))
      (node (ref "U13") (pin "2") (pinfunction "QC_2") (pintype "tri_state"))
      (node (ref "U14") (pin "3") (pinfunction "I3_3") (pintype "input"))
    )
    (net (code "123") (name "Net-(U13A-QD)") (class "Default")
      (node (ref "R64") (pin "1") (pinfunction "1_1") (pintype "passive"))
      (node (ref "U13") (pin "3") (pinfunction "QD_3") (pintype "tri_state"))
      (node (ref "U14") (pin "4") (pinfunction "I4_4") (pintype "input"))
    )
    (net (code "124") (name "Net-(U13A-QE)") (class "Default")
      (node (ref "R63") (pin "1") (pinfunction "1_1") (pintype "passive"))
      (node (ref "U13") (pin "4") (pinfunction "QE_4") (pintype "tri_state"))
      (node (ref "U14") (pin "5") (pinfunction "I5_5") (pintype "input"))
    )
    (net (code "125") (name "Net-(U13A-QF)") (class "Default")
      (node (ref "R62") (pin "1") (pinfunction "1_1") (pintype "passive"))
      (node (ref "U13") (pin "5") (pinfunction "QF_5") (pintype "tri_state"))
      (node (ref "U14") (pin "6") (pinfunction "I6_6") (pintype "input"))
    )
    (net (code "126") (name "Net-(U13A-QG)") (class "Default")
      (node (ref "R61") (pin "1") (pinfunction "1_1") (pintype "passive"))
      (node (ref "U13") (pin "6") (pinfunction "QG_6") (pintype "tri_state"))
      (node (ref "U14") (pin "7") (pinfunction "I7_7") (pintype "input"))
    )
    (net (code "127") (name "Net-(U13A-QH)") (class "Default")
      (node (ref "R60") (pin "1") (pinfunction "1_1") (pintype "passive"))
      (node (ref "U13") (pin "7") (pinfunction "QH_7") (pintype "tri_state"))
      (node (ref "U14") (pin "8") (pinfunction "I8_8") (pintype "input"))
    )
    (net (code "128") (name "Net-(X1-Pad4)") (class "Default")
      (node (ref "X1") (pin "4") (pinfunction "4_4") (pintype "passive"))
      (node (ref "X2") (pin "4") (pinfunction "4_4") (pintype "passive"))
    )
    (net (code "129") (name "Net-(X1-Pad5)") (class "Default")
      (node (ref "X1") (pin "5") (pinfunction "5_5") (pintype "passive"))
      (node (ref "X2") (pin "5") (pinfunction "5_5") (pintype "passive"))
    )
    (net (code "130") (name "OLAT") (class "Default")
      (node (ref "G1") (pin "PA8") (pinfunction "PA8_PA8") (pintype "bidirectional"))
      (node (ref "R3") (pin "1") (pinfunction "1_1") (pintype "passive"))
      (node (ref "U11") (pin "12") (pinfunction "RCK_12") (pintype "input"))
      (node (ref "U13") (pin "12") (pinfunction "RCK_12") (pintype "input"))
    )
    (net (code "131") (name "SCK") (class "Default")
      (node (ref "G1") (pin "PB3") (pinfunction "PB3_PB3") (pintype "bidirectional"))
      (node (ref "JP5") (pin "3") (pinfunction "3_3") (pintype "passive"))
      (node (ref "R5") (pin "1") (pinfunction "1_1") (pintype "passive"))
      (node (ref "U11") (pin "11") (pinfunction "SCK_11") (pintype "input"))
      (node (ref "U13") (pin "11") (pinfunction "SCK_11") (pintype "input"))
    )
    (net (code "132") (name "SCK2") (class "Default")
      (node (ref "G1") (pin "PB10") (pinfunction "PB10_PB10") (pintype "bidirectional"))
      (node (ref "SJ2") (pin "P$1") (pinfunction "1_P$1") (pintype "passive"))
      (node (ref "U3") (pin "7") (pinfunction "CLK_7") (pintype "input"))
      (node (ref "U4") (pin "7") (pinfunction "CLK_7") (pintype "input"))
    )
    (net (code "133") (name "SLNK1") (class "Default")
      (node (ref "SJ14") (pin "P$1") (pinfunction "1_P$1") (pintype "passive"))
      (node (ref "U11") (pin "14") (pinfunction "SER_14") (pintype "input"))
      (node (ref "U13") (pin "9") (pinfunction "QH*_9") (pintype "tri_state"))
    )
    (net (code "134") (name "SLNK2") (class "Default")
      (node (ref "SJ5") (pin "P$1") (pinfunction "1_P$1") (pintype "passive"))
      (node (ref "U11") (pin "9") (pinfunction "QH*_9") (pintype "tri_state"))
    )
    (net (code "135") (name "SLNK3") (class "Default")
      (node (ref "SJ7") (pin "P$1") (pinfunction "1_P$1") (pintype "passive"))
      (node (ref "U3") (pin "1") (pinfunction "SER_1") (pintype "input"))
      (node (ref "U4") (pin "13") (pinfunction "QH_13") (pintype "output"))
    )
    (net (code "136") (name "SRV1") (class "Default")
      (node (ref "G1") (pin "PC9") (pinfunction "PC9_PC9") (pintype "bidirectional"))
      (node (ref "JP4") (pin "2") (pinfunction "2_2") (pintype "passive"))
      (node (ref "R13") (pin "2") (pinfunction "2_2") (pintype "passive"))
    )
    (net (code "137") (name "SRV2") (class "Default")
      (node (ref "G1") (pin "PC7") (pinfunction "PC7_PC7") (pintype "bidirectional"))
      (node (ref "JP4") (pin "1") (pinfunction "1_1") (pintype "passive"))
      (node (ref "R12") (pin "2") (pinfunction "2_2") (pintype "passive"))
    )
    (net (code "138") (name "SRV3") (class "Default")
      (node (ref "G1") (pin "PC8") (pinfunction "PC8_PC8") (pintype "bidirectional"))
      (node (ref "JP3") (pin "2") (pinfunction "2_2") (pintype "passive"))
      (node (ref "R11") (pin "2") (pinfunction "2_2") (pintype "passive"))
    )
    (net (code "139") (name "SRV4") (class "Default")
      (node (ref "G1") (pin "PC6") (pinfunction "PC6_PC6") (pintype "bidirectional"))
      (node (ref "JP3") (pin "1") (pinfunction "1_1") (pintype "passive"))
      (node (ref "R10") (pin "2") (pinfunction "2_2") (pintype "passive"))
    )
    (net (code "140") (name "SRV5") (class "Default")
      (node (ref "G1") (pin "PF1-PH1") (pinfunction "PF1-PH1_PF1-PH1") (pintype "bidirectional"))
      (node (ref "JP2") (pin "2") (pinfunction "2_2") (pintype "passive"))
      (node (ref "R9") (pin "2") (pinfunction "2_2") (pintype "passive"))
    )
    (net (code "141") (name "SRV6") (class "Default")
      (node (ref "G1") (pin "PA15") (pinfunction "PA15_PA15") (pintype "bidirectional"))
      (node (ref "JP2") (pin "1") (pinfunction "1_1") (pintype "passive"))
      (node (ref "R8") (pin "2") (pinfunction "2_2") (pintype "passive"))
    )
    (net (code "142") (name "SRV7") (class "Default")
      (node (ref "G1") (pin "PC12") (pinfunction "PC12_PC12") (pintype "bidirectional"))
      (node (ref "JP1") (pin "2") (pinfunction "2_2") (pintype "passive"))
      (node (ref "R7") (pin "2") (pinfunction "2_2") (pintype "passive"))
    )
    (net (code "143") (name "SRV8") (class "Default")
      (node (ref "G1") (pin "PD2") (pinfunction "PD2_PD2") (pintype "bidirectional"))
      (node (ref "JP1") (pin "1") (pinfunction "1_1") (pintype "passive"))
      (node (ref "R6") (pin "2") (pinfunction "2_2") (pintype "passive"))
    )
    (net (code "144") (name "TDRV1") (class "Default")
      (node (ref "G1") (pin "PB12") (pinfunction "PB12_PB12") (pintype "bidirectional"))
      (node (ref "U10") (pin "2") (pinfunction "I_2") (pintype "input"))
      (node (ref "U9") (pin "12") (pinfunction "+IN_12") (pintype "input"))
    )
    (net (code "145") (name "TDRV2") (class "Default")
      (node (ref "G1") (pin "PB2") (pinfunction "PB2_PB2") (pintype "bidirectional"))
      (node (ref "U10") (pin "4") (pinfunction "I_4") (pintype "input"))
      (node (ref "U9") (pin "3") (pinfunction "+IN_3") (pintype "input"))
    )
    (net (code "146") (name "TDRV3") (class "Default")
      (node (ref "G1") (pin "PB15") (pinfunction "PB15_PB15") (pintype "bidirectional"))
      (node (ref "U8") (pin "4") (pinfunction "I_4") (pintype "input"))
      (node (ref "U9") (pin "10") (pinfunction "+IN_10") (pintype "input"))
    )
    (net (code "147") (name "TDRV4") (class "Default")
      (node (ref "G1") (pin "PB1") (pinfunction "PB1_PB1") (pintype "bidirectional"))
      (node (ref "U8") (pin "2") (pinfunction "I_2") (pintype "input"))
      (node (ref "U9") (pin "5") (pinfunction "+IN_5") (pintype "input"))
    )
    (net (code "148") (name "TDRV5") (class "Default")
      (node (ref "G1") (pin "PA0") (pinfunction "PA0_PA0") (pintype "bidirectional"))
      (node (ref "U6") (pin "12") (pinfunction "+IN_12") (pintype "input"))
      (node (ref "U7") (pin "2") (pinfunction "I_2") (pintype "input"))
    )
    (net (code "149") (name "TDRV6") (class "Default")
      (node (ref "G1") (pin "PA4") (pinfunction "PA4_PA4") (pintype "bidirectional"))
      (node (ref "U6") (pin "3") (pinfunction "+IN_3") (pintype "input"))
      (node (ref "U7") (pin "4") (pinfunction "I_4") (pintype "input"))
    )
    (net (code "150") (name "TDRV7") (class "Default")
      (node (ref "G1") (pin "PC3") (pinfunction "PC3_PC3") (pintype "bidirectional"))
      (node (ref "U5") (pin "4") (pinfunction "I_4") (pintype "input"))
      (node (ref "U6") (pin "10") (pinfunction "+IN_10") (pintype "input"))
    )
    (net (code "151") (name "TDRV8") (class "Default")
      (node (ref "G1") (pin "PC0") (pinfunction "PC0_PC0") (pintype "bidirectional"))
      (node (ref "U5") (pin "2") (pinfunction "I_2") (pintype "input"))
      (node (ref "U6") (pin "5") (pinfunction "+IN_5") (pintype "input"))
    )
    (net (code "152") (name "V+") (class "Default")
      (node (ref "C6") (pin "+") (pinfunction "+_+") (pintype "passive"))
      (node (ref "C7") (pin "1") (pinfunction "1_1") (pintype "passive"))
      (node (ref "G1") (pin "E5V") (pinfunction "E5V_E5V") (pintype "power_in"))
      (node (ref "IC1") (pin "1") (pinfunction "FB_1") (pintype "input"))
      (node (ref "L1") (pin "1") (pinfunction "1_1") (pintype "passive"))
      (node (ref "U2") (pin "3") (pinfunction "FB_3") (pintype "bidirectional"))
    )
    (net (code "153") (name "unconnected-(G1-PadBOOT0)") (class "Default")
      (node (ref "G1") (pin "BOOT0") (pinfunction "BOOT0_BOOT0") (pintype "bidirectional"))
    )
    (net (code "154") (name "unconnected-(G1-PadIOREF2)") (class "Default")
      (node (ref "G1") (pin "IOREF2") (pinfunction "IOREF2_IOREF2") (pintype "input"))
    )
    (net (code "155") (name "unconnected-(G1-PadNC1-PF7)") (class "Default")
      (node (ref "G1") (pin "NC1-PF7") (pinfunction "NC1-PF7_NC1-PF7") (pintype "bidirectional"))
    )
    (net (code "156") (name "unconnected-(G1-PadNC2-PF6)") (class "Default")
      (node (ref "G1") (pin "NC2-PF6") (pinfunction "NC2-PF6_NC2-PF6") (pintype "bidirectional"))
    )
    (net (code "157") (name "unconnected-(G1-PadNC3)") (class "Default")
      (node (ref "G1") (pin "NC3") (pinfunction "NC3_NC3") (pintype "no_connect"))
    )
    (net (code "158") (name "unconnected-(G1-PadNC4)") (class "Default")
      (node (ref "G1") (pin "NC4") (pinfunction "NC4_NC4") (pintype "no_connect"))
    )
    (net (code "159") (name "unconnected-(G1-PadNC5-PD8)") (class "Default")
      (node (ref "G1") (pin "NC5-PD8") (pinfunction "NC5-PD8_NC5-PD8") (pintype "bidirectional"))
    )
    (net (code "160") (name "unconnected-(G1-PadNC6-PB11)") (class "Default")
      (node (ref "G1") (pin "NC6-PB11") (pinfunction "NC6-PB11_NC6-PB11") (pintype "no_connect"))
    )
    (net (code "161") (name "unconnected-(G1-PadNC7-PF5)") (class "Default")
      (node (ref "G1") (pin "NC7-PF5") (pinfunction "NC7-PF5_NC7-PF5") (pintype "bidirectional"))
    )
    (net (code "162") (name "unconnected-(G1-PadNC8-PF4)") (class "Default")
      (node (ref "G1") (pin "NC8-PF4") (pinfunction "NC8-PF4_NC8-PF4") (pintype "bidirectional"))
    )
    (net (code "163") (name "unconnected-(G1-PadNRESET)") (class "Default")
      (node (ref "G1") (pin "NRESET") (pinfunction "NRESET_NRESET") (pintype "input"))
    )
    (net (code "164") (name "unconnected-(G1-PadPA1)") (class "Default")
      (node (ref "G1") (pin "PA1") (pinfunction "PA1_PA1") (pintype "bidirectional"))
    )
    (net (code "165") (name "unconnected-(G1-PadPA2)") (class "Default")
      (node (ref "G1") (pin "PA2") (pinfunction "PA2_PA2") (pintype "bidirectional"))
    )
    (net (code "166") (name "unconnected-(G1-PadPA3)") (class "Default")
      (node (ref "G1") (pin "PA3") (pinfunction "PA3_PA3") (pintype "bidirectional"))
    )
    (net (code "167") (name "unconnected-(G1-PadPA5)") (class "Default")
      (node (ref "G1") (pin "PA5") (pinfunction "PA5_PA5") (pintype "bidirectional"))
    )
    (net (code "168") (name "unconnected-(G1-PadPA7)") (class "Default")
      (node (ref "G1") (pin "PA7") (pinfunction "PA7_PA7") (pintype "bidirectional"))
    )
    (net (code "169") (name "unconnected-(G1-PadPA9)") (class "Default")
      (node (ref "G1") (pin "PA9") (pinfunction "PA9_PA9") (pintype "bidirectional"))
    )
    (net (code "170") (name "unconnected-(G1-PadPA10)") (class "Default")
      (node (ref "G1") (pin "PA10") (pinfunction "PA10_PA10") (pintype "bidirectional"))
    )
    (net (code "171") (name "unconnected-(G1-PadPA11)") (class "Default")
      (node (ref "G1") (pin "PA11") (pinfunction "PA11_PA11") (pintype "bidirectional"))
    )
    (net (code "172") (name "unconnected-(G1-PadPA12)") (class "Default")
      (node (ref "G1") (pin "PA12") (pinfunction "PA12_PA12") (pintype "bidirectional"))
    )
    (net (code "173") (name "unconnected-(G1-PadPA13)") (class "Default")
      (node (ref "G1") (pin "PA13") (pinfunction "PA13_PA13") (pintype "bidirectional"))
    )
    (net (code "174") (name "unconnected-(G1-PadPA14)") (class "Default")
      (node (ref "G1") (pin "PA14") (pinfunction "PA14_PA14") (pintype "bidirectional"))
    )
    (net (code "175") (name "unconnected-(G1-PadPB0)") (class "Default")
      (node (ref "G1") (pin "PB0") (pinfunction "PB0_PB0") (pintype "bidirectional"))
    )
    (net (code "176") (name "unconnected-(G1-PadPC1)") (class "Default")
      (node (ref "G1") (pin "PC1") (pinfunction "PC1_PC1") (pintype "bidirectional"))
    )
    (net (code "177") (name "unconnected-(G1-PadPC4)") (class "Default")
      (node (ref "G1") (pin "PC4") (pinfunction "PC4_PC4") (pintype "bidirectional"))
    )
    (net (code "178") (name "unconnected-(G1-PadPC5)") (class "Default")
      (node (ref "G1") (pin "PC5") (pinfunction "PC5_PC5") (pintype "bidirectional"))
    )
    (net (code "179") (name "unconnected-(G1-PadPC13)") (class "Default")
      (node (ref "G1") (pin "PC13") (pinfunction "PC13_PC13") (pintype "bidirectional"))
    )
    (net (code "180") (name "unconnected-(G1-PadPC14)") (class "Default")
      (node (ref "G1") (pin "PC14") (pinfunction "PC14_PC14") (pintype "bidirectional"))
    )
    (net (code "181") (name "unconnected-(G1-PadPC15)") (class "Default")
      (node (ref "G1") (pin "PC15") (pinfunction "PC15_PC15") (pintype "bidirectional"))
    )
    (net (code "182") (name "unconnected-(G1-PadPF0-PH0)") (class "Default")
      (node (ref "G1") (pin "PF0-PH0") (pinfunction "PF0-PH0_PF0-PH0") (pintype "bidirectional"))
    )
    (net (code "183") (name "unconnected-(H1-MOUNT-PadB3,3)") (class "Default")
      (node (ref "H1") (pin "B3,3") (pinfunction "MOUNT_B3,3") (pintype "passive"))
    )
    (net (code "184") (name "unconnected-(H2-MOUNT-PadB3,3)") (class "Default")
      (node (ref "H2") (pin "B3,3") (pinfunction "MOUNT_B3,3") (pintype "passive"))
    )
    (net (code "185") (name "unconnected-(H3-MOUNT-PadB3,3)") (class "Default")
      (node (ref "H3") (pin "B3,3") (pinfunction "MOUNT_B3,3") (pintype "passive"))
    )
    (net (code "186") (name "unconnected-(H4-MOUNT-PadB3,3)") (class "Default")
      (node (ref "H4") (pin "B3,3") (pinfunction "MOUNT_B3,3") (pintype "passive"))
    )
  )
)
